# coil-control-rev.net
KiCad netlist of a schematic drawn in EAGLE
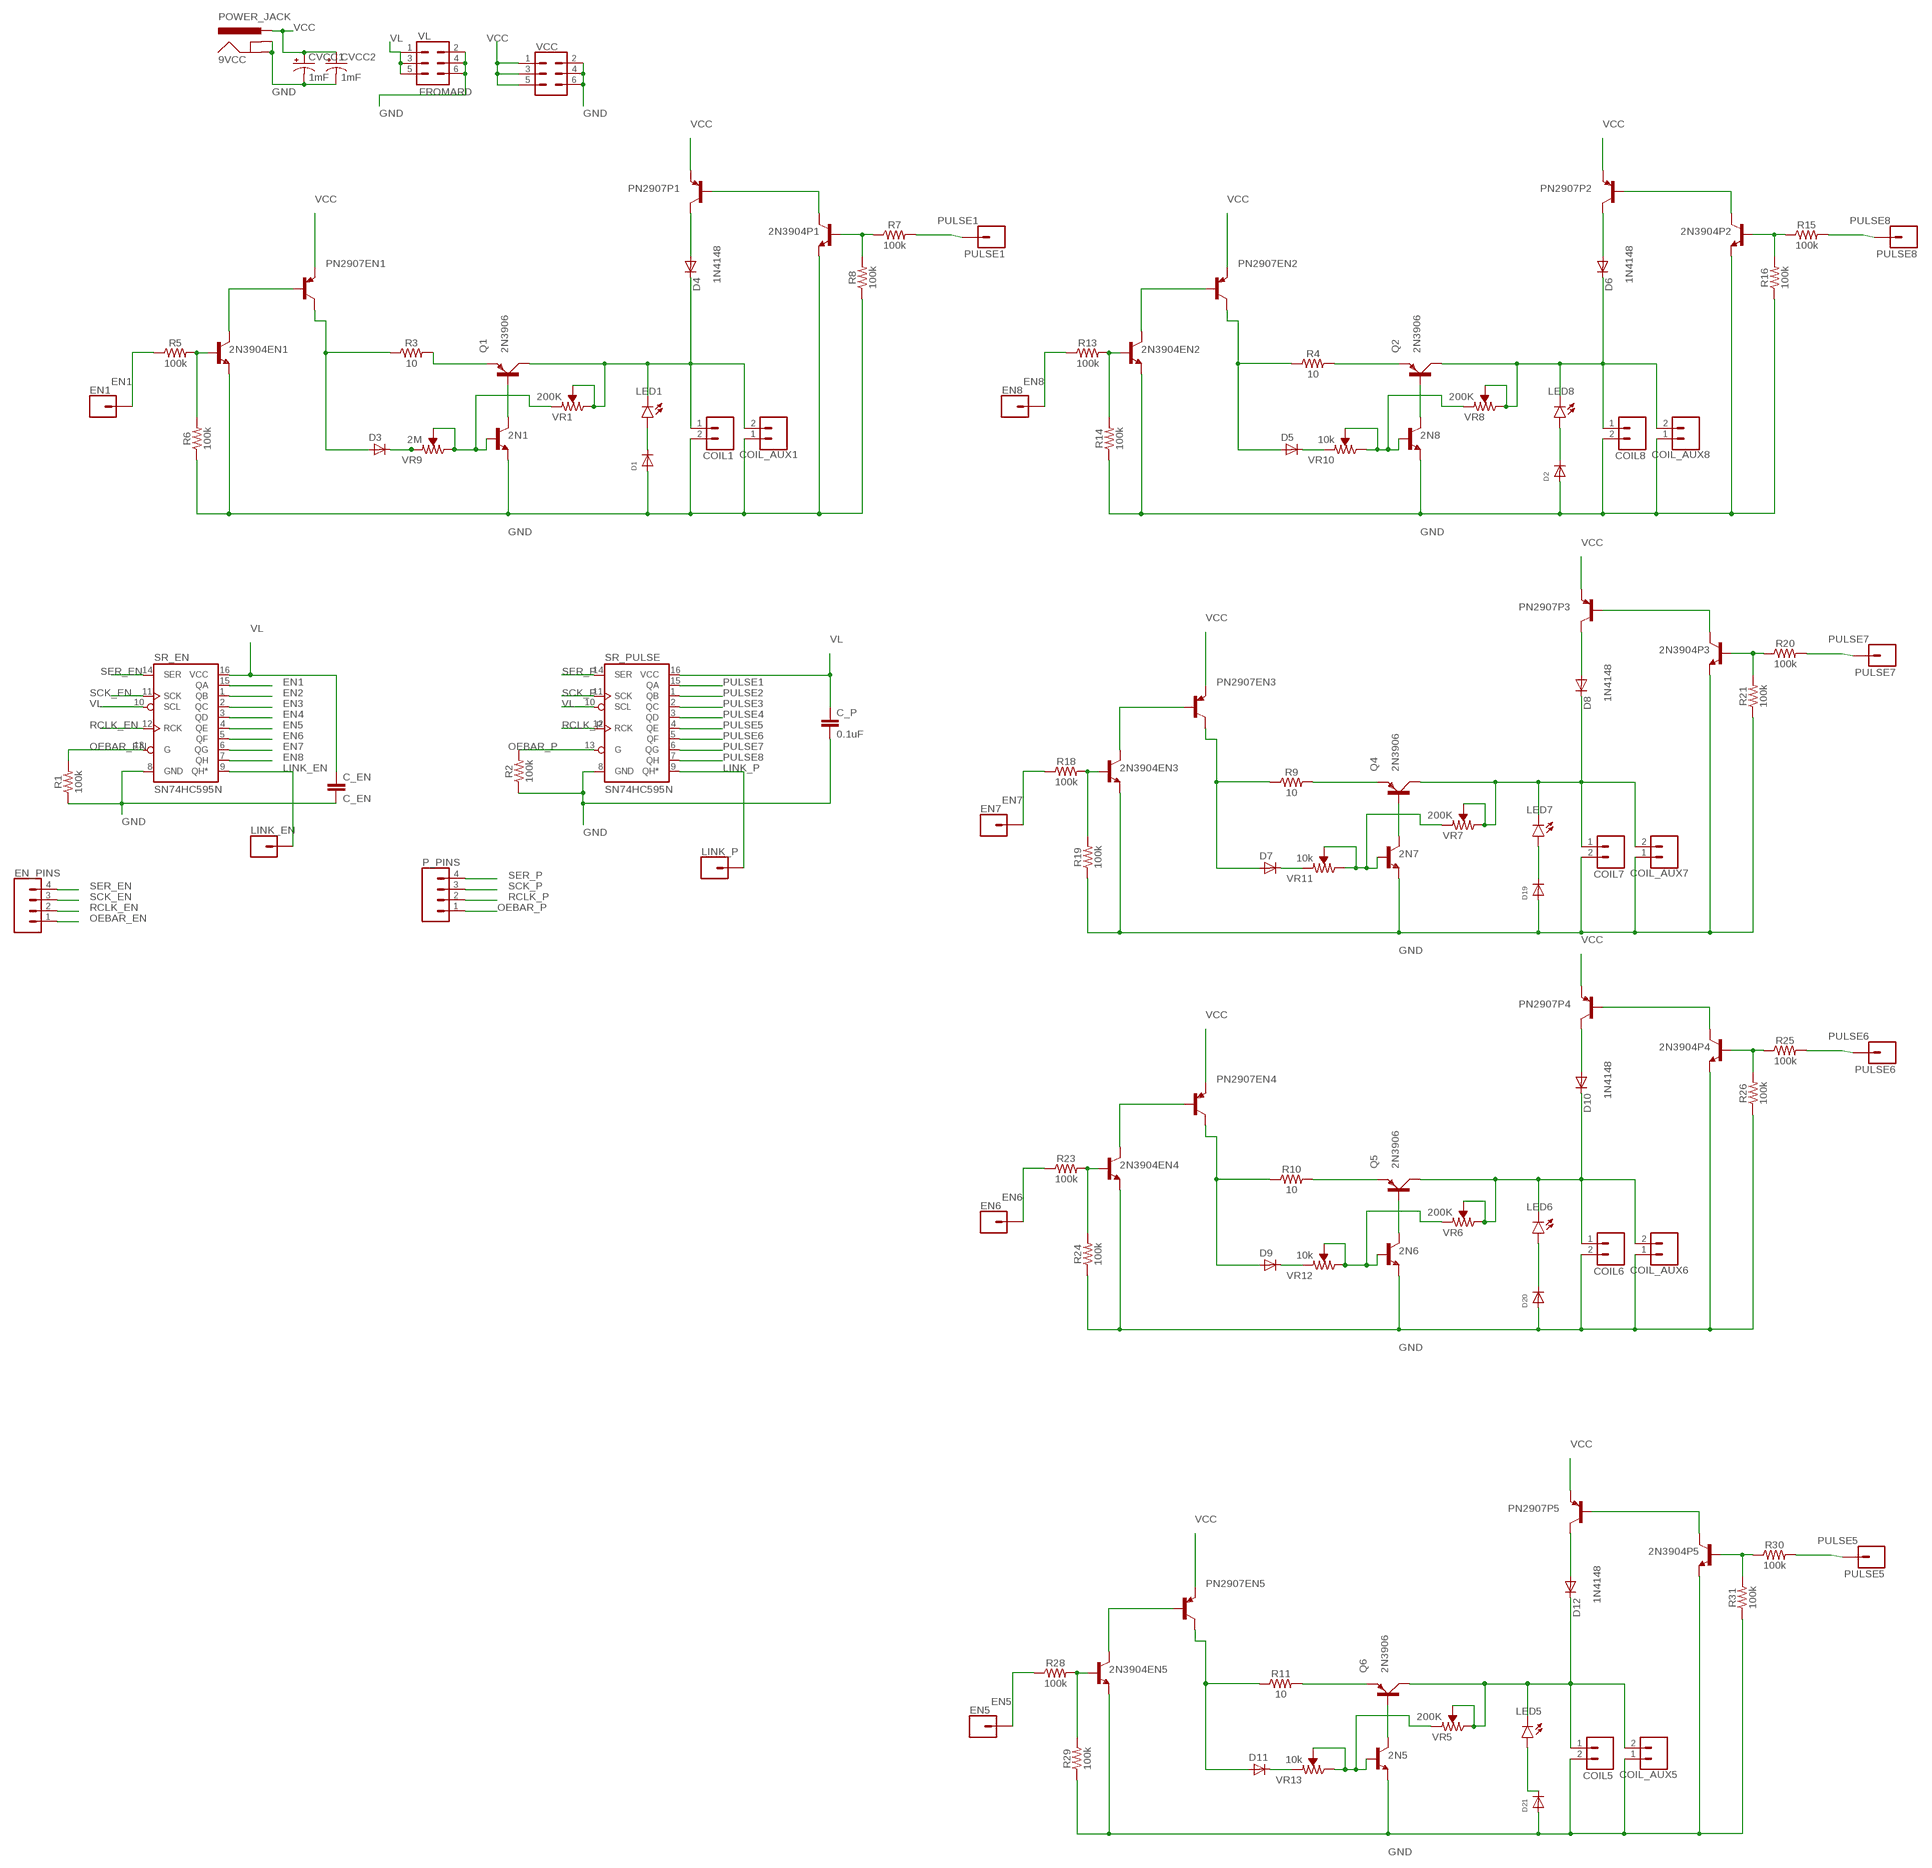
[diagram p0: schematic, sheet 1, part 1 of 2]
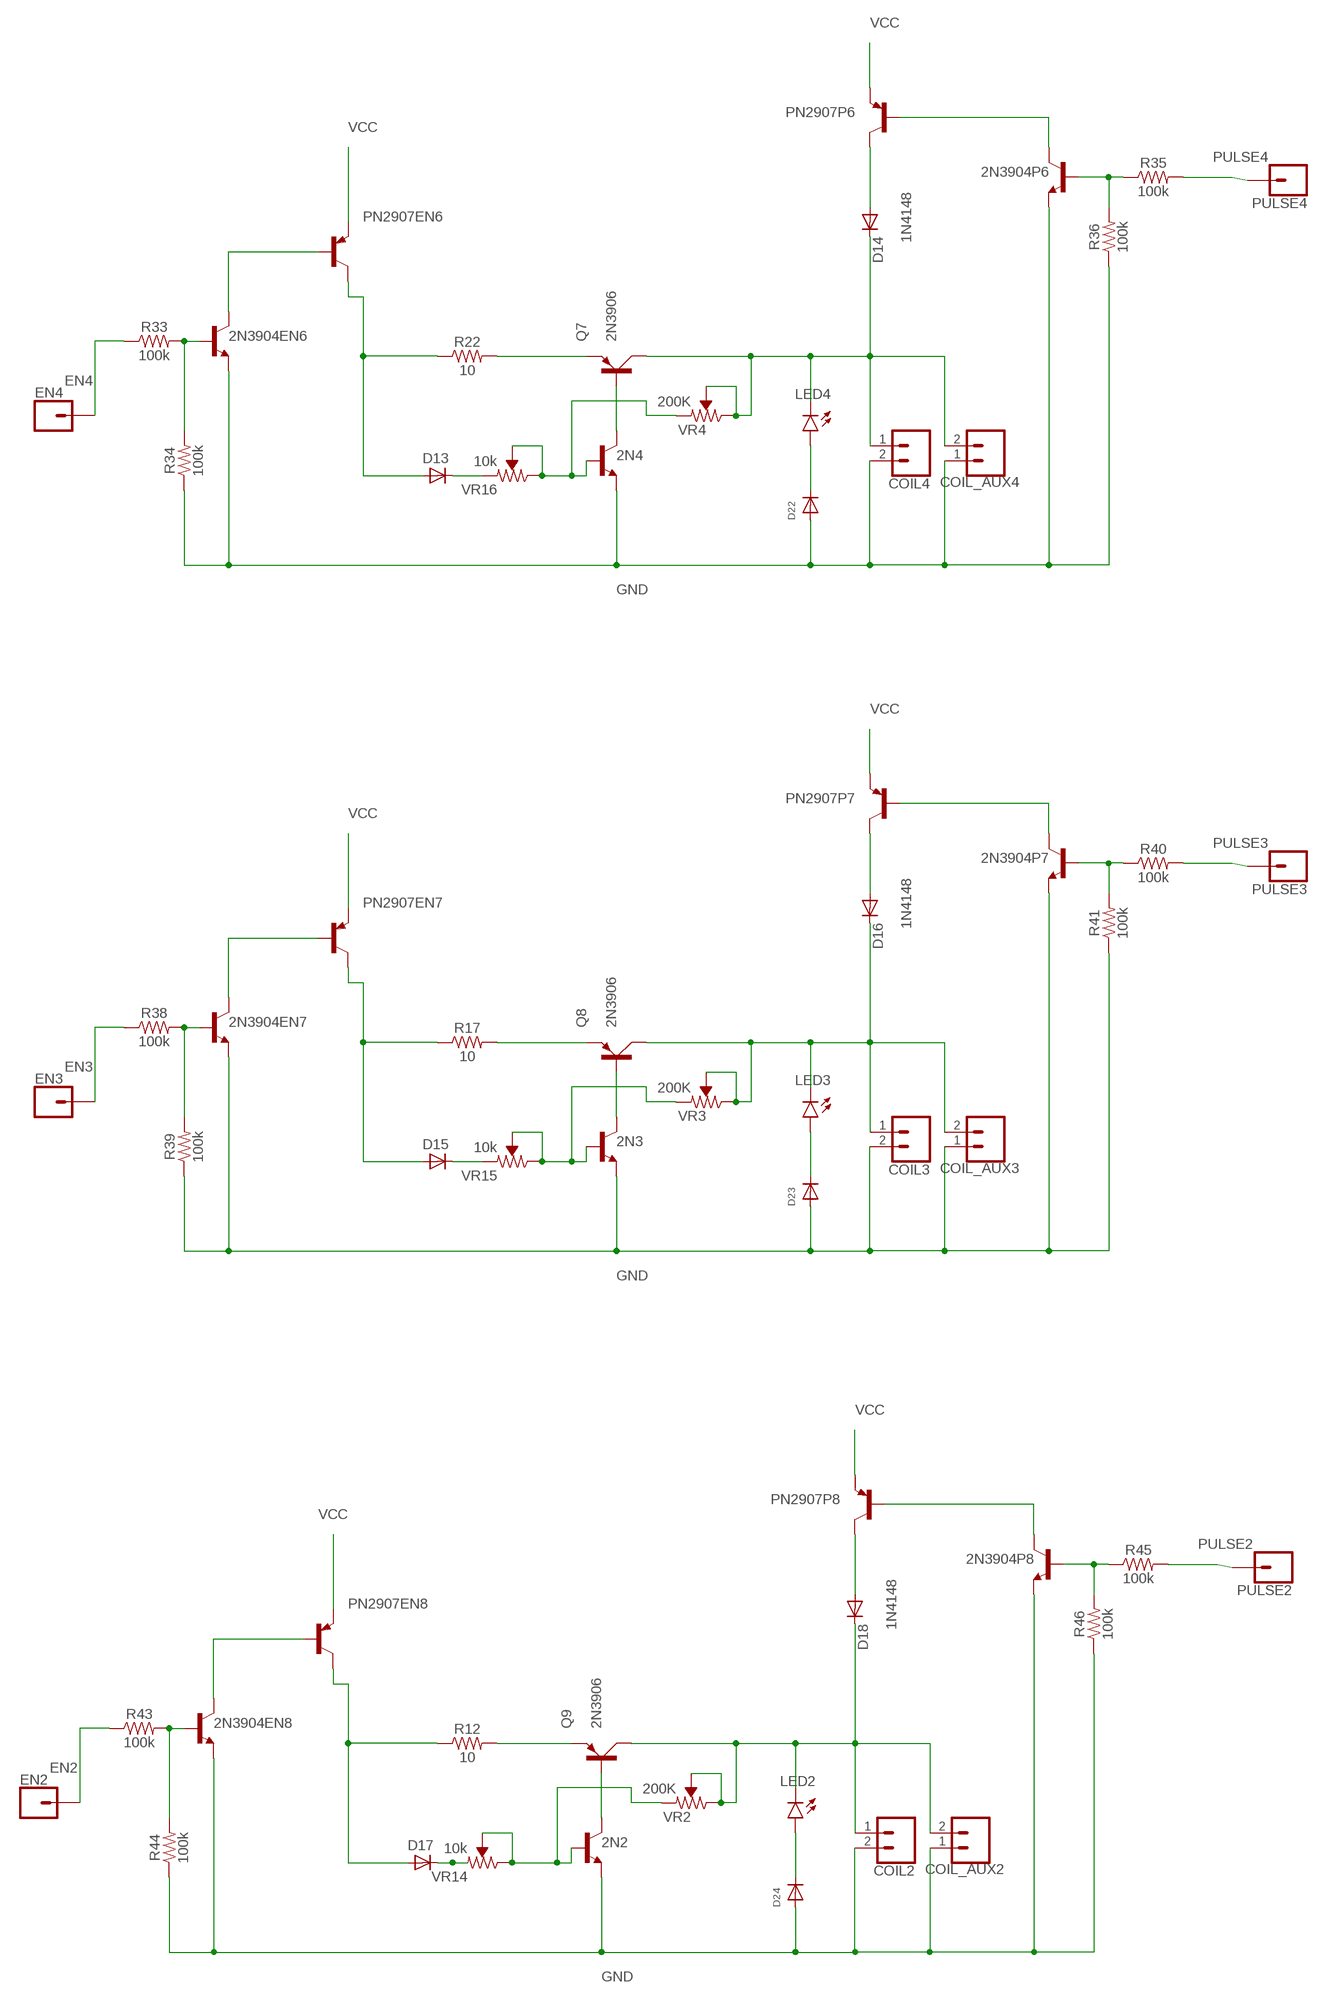
[diagram p1: schematic, sheet 1, part 2 of 2]

(export (version "E")
  (design (tool "Eeschema 10.0.6"))
  (components
    (comp (ref "2N1")
      (value "2N2222")
      (footprint "eagle-import:TO92-EBC-OVAL")
      (libsource (lib "eagle-import") (part "2N2222"))
    )
    (comp (ref "2N2")
      (value "2N2222")
      (footprint "eagle-import:TO92-EBC-OVAL")
      (libsource (lib "eagle-import") (part "2N2222"))
    )
    (comp (ref "2N3")
      (value "2N2222")
      (footprint "eagle-import:TO92-EBC-OVAL")
      (libsource (lib "eagle-import") (part "2N2222"))
    )
    (comp (ref "2N4")
      (value "2N2222")
      (footprint "eagle-import:TO92-EBC-OVAL")
      (libsource (lib "eagle-import") (part "2N2222"))
    )
    (comp (ref "2N5")
      (value "2N2222")
      (footprint "eagle-import:TO92-EBC-OVAL")
      (libsource (lib "eagle-import") (part "2N2222"))
    )
    (comp (ref "2N6")
      (value "2N2222")
      (footprint "eagle-import:TO92-EBC-OVAL")
      (libsource (lib "eagle-import") (part "2N2222"))
    )
    (comp (ref "2N7")
      (value "2N2222")
      (footprint "eagle-import:TO92-EBC-OVAL")
      (libsource (lib "eagle-import") (part "2N2222"))
    )
    (comp (ref "2N8")
      (value "2N2222")
      (footprint "eagle-import:TO92-EBC-OVAL")
      (libsource (lib "eagle-import") (part "2N2222"))
    )
    (comp (ref "2N3904EN1")
      (value "2N3904")
      (footprint "eagle-import:TO92")
      (libsource (lib "eagle-import") (part "2N3904"))
    )
    (comp (ref "2N3904EN2")
      (value "2N3904")
      (footprint "eagle-import:TO92")
      (libsource (lib "eagle-import") (part "2N3904"))
    )
    (comp (ref "2N3904EN3")
      (value "2N3904")
      (footprint "eagle-import:TO92")
      (libsource (lib "eagle-import") (part "2N3904"))
    )
    (comp (ref "2N3904EN4")
      (value "2N3904")
      (footprint "eagle-import:TO92")
      (libsource (lib "eagle-import") (part "2N3904"))
    )
    (comp (ref "2N3904EN5")
      (value "2N3904")
      (footprint "eagle-import:TO92")
      (libsource (lib "eagle-import") (part "2N3904"))
    )
    (comp (ref "2N3904EN6")
      (value "2N3904")
      (footprint "eagle-import:TO92")
      (libsource (lib "eagle-import") (part "2N3904"))
    )
    (comp (ref "2N3904EN7")
      (value "2N3904")
      (footprint "eagle-import:TO92")
      (libsource (lib "eagle-import") (part "2N3904"))
    )
    (comp (ref "2N3904EN8")
      (value "2N3904")
      (footprint "eagle-import:TO92")
      (libsource (lib "eagle-import") (part "2N3904"))
    )
    (comp (ref "2N3904P1")
      (value "2N3904")
      (footprint "eagle-import:TO92")
      (libsource (lib "eagle-import") (part "2N3904"))
    )
    (comp (ref "2N3904P2")
      (value "2N3904")
      (footprint "eagle-import:TO92")
      (libsource (lib "eagle-import") (part "2N3904"))
    )
    (comp (ref "2N3904P3")
      (value "2N3904")
      (footprint "eagle-import:TO92")
      (libsource (lib "eagle-import") (part "2N3904"))
    )
    (comp (ref "2N3904P4")
      (value "2N3904")
      (footprint "eagle-import:TO92")
      (libsource (lib "eagle-import") (part "2N3904"))
    )
    (comp (ref "2N3904P5")
      (value "2N3904")
      (footprint "eagle-import:TO92")
      (libsource (lib "eagle-import") (part "2N3904"))
    )
    (comp (ref "2N3904P6")
      (value "2N3904")
      (footprint "eagle-import:TO92")
      (libsource (lib "eagle-import") (part "2N3904"))
    )
    (comp (ref "2N3904P7")
      (value "2N3904")
      (footprint "eagle-import:TO92")
      (libsource (lib "eagle-import") (part "2N3904"))
    )
    (comp (ref "2N3904P8")
      (value "2N3904")
      (footprint "eagle-import:TO92")
      (libsource (lib "eagle-import") (part "2N3904"))
    )
    (comp (ref "9VCC")
      (value "POWER_JACK")
      (footprint "eagle-import:POWER_JACK_PTH")
      (libsource (lib "eagle-import") (part "POWER_JACK"))
    )
    (comp (ref "COIL1")
      (value "CONN_02")
      (footprint "eagle-import:1X02")
      (libsource (lib "eagle-import") (part "CONN_02"))
    )
    (comp (ref "COIL2")
      (value "CONN_02")
      (footprint "eagle-import:1X02")
      (libsource (lib "eagle-import") (part "CONN_02"))
    )
    (comp (ref "COIL3")
      (value "CONN_02")
      (footprint "eagle-import:1X02")
      (libsource (lib "eagle-import") (part "CONN_02"))
    )
    (comp (ref "COIL4")
      (value "CONN_02")
      (footprint "eagle-import:1X02")
      (libsource (lib "eagle-import") (part "CONN_02"))
    )
    (comp (ref "COIL5")
      (value "CONN_02")
      (footprint "eagle-import:1X02")
      (libsource (lib "eagle-import") (part "CONN_02"))
    )
    (comp (ref "COIL6")
      (value "CONN_02")
      (footprint "eagle-import:1X02")
      (libsource (lib "eagle-import") (part "CONN_02"))
    )
    (comp (ref "COIL7")
      (value "CONN_02")
      (footprint "eagle-import:1X02")
      (libsource (lib "eagle-import") (part "CONN_02"))
    )
    (comp (ref "COIL8")
      (value "CONN_02")
      (footprint "eagle-import:1X02")
      (libsource (lib "eagle-import") (part "CONN_02"))
    )
    (comp (ref "COIL_AUX1")
      (value "CONN_02")
      (footprint "eagle-import:1X02")
      (libsource (lib "eagle-import") (part "CONN_02"))
    )
    (comp (ref "COIL_AUX2")
      (value "CONN_02")
      (footprint "eagle-import:1X02")
      (libsource (lib "eagle-import") (part "CONN_02"))
    )
    (comp (ref "COIL_AUX3")
      (value "CONN_02")
      (footprint "eagle-import:1X02")
      (libsource (lib "eagle-import") (part "CONN_02"))
    )
    (comp (ref "COIL_AUX4")
      (value "CONN_02")
      (footprint "eagle-import:1X02")
      (libsource (lib "eagle-import") (part "CONN_02"))
    )
    (comp (ref "COIL_AUX5")
      (value "CONN_02")
      (footprint "eagle-import:1X02")
      (libsource (lib "eagle-import") (part "CONN_02"))
    )
    (comp (ref "COIL_AUX6")
      (value "CONN_02")
      (footprint "eagle-import:1X02")
      (libsource (lib "eagle-import") (part "CONN_02"))
    )
    (comp (ref "COIL_AUX7")
      (value "CONN_02")
      (footprint "eagle-import:1X02")
      (libsource (lib "eagle-import") (part "CONN_02"))
    )
    (comp (ref "COIL_AUX8")
      (value "CONN_02")
      (footprint "eagle-import:1X02")
      (libsource (lib "eagle-import") (part "CONN_02"))
    )
    (comp (ref "CVCC1")
      (value "1mF")
      (footprint "eagle-import:CPOL-RADIAL-5MM-10MM")
      (libsource (lib "eagle-import") (part "1000UF-RADIAL-5MM-25V-20%"))
    )
    (comp (ref "CVCC2")
      (value "1mF")
      (footprint "eagle-import:CPOL-RADIAL-5MM-10MM")
      (libsource (lib "eagle-import") (part "1000UF-RADIAL-5MM-25V-20%"))
    )
    (comp (ref "C_EN")
      (value "C_EN")
      (footprint "eagle-import:CAP-PTH-SMALL-KIT")
      (libsource (lib "eagle-import") (part "0.1UF-KIT-EZ-50V-20%"))
    )
    (comp (ref "C_P")
      (value "0.1uF")
      (footprint "eagle-import:CAP-PTH-SMALL-KIT")
      (libsource (lib "eagle-import") (part "0.1UF-KIT-EZ-50V-20%"))
    )
    (comp (ref "D1")
      (value "DIODEDO-1N4148")
      (footprint "eagle-import:DO-1N4148")
      (libsource (lib "eagle-import") (part "DIODEDO-1N4148"))
    )
    (comp (ref "D2")
      (value "DIODEDO-1N4148")
      (footprint "eagle-import:DO-1N4148")
      (libsource (lib "eagle-import") (part "DIODEDO-1N4148"))
    )
    (comp (ref "D3")
      (value "DIODEDO-1N4148")
      (footprint "eagle-import:DO-1N4148")
      (libsource (lib "eagle-import") (part "DIODEDO-1N4148"))
    )
    (comp (ref "D4")
      (value "1N4148")
      (footprint "eagle-import:DO-1N4148")
      (libsource (lib "eagle-import") (part "DIODEDO-1N4148"))
    )
    (comp (ref "D5")
      (value "DIODEDO-1N4148")
      (footprint "eagle-import:DO-1N4148")
      (libsource (lib "eagle-import") (part "DIODEDO-1N4148"))
    )
    (comp (ref "D6")
      (value "1N4148")
      (footprint "eagle-import:DO-1N4148")
      (libsource (lib "eagle-import") (part "DIODEDO-1N4148"))
    )
    (comp (ref "D7")
      (value "DIODEDO-1N4148")
      (footprint "eagle-import:DO-1N4148")
      (libsource (lib "eagle-import") (part "DIODEDO-1N4148"))
    )
    (comp (ref "D8")
      (value "1N4148")
      (footprint "eagle-import:DO-1N4148")
      (libsource (lib "eagle-import") (part "DIODEDO-1N4148"))
    )
    (comp (ref "D9")
      (value "DIODEDO-1N4148")
      (footprint "eagle-import:DO-1N4148")
      (libsource (lib "eagle-import") (part "DIODEDO-1N4148"))
    )
    (comp (ref "D10")
      (value "1N4148")
      (footprint "eagle-import:DO-1N4148")
      (libsource (lib "eagle-import") (part "DIODEDO-1N4148"))
    )
    (comp (ref "D11")
      (value "200mA/100V/1V")
      (footprint "eagle-import:DO-1N4148")
      (libsource (lib "eagle-import") (part "DIODEDO-1N4148"))
    )
    (comp (ref "D12")
      (value "1N4148")
      (footprint "eagle-import:DO-1N4148")
      (libsource (lib "eagle-import") (part "DIODEDO-1N4148"))
    )
    (comp (ref "D13")
      (value "DIODEDO-1N4148")
      (footprint "eagle-import:DO-1N4148")
      (libsource (lib "eagle-import") (part "DIODEDO-1N4148"))
    )
    (comp (ref "D14")
      (value "1N4148")
      (footprint "eagle-import:DO-1N4148")
      (libsource (lib "eagle-import") (part "DIODEDO-1N4148"))
    )
    (comp (ref "D15")
      (value "DIODEDO-1N4148")
      (footprint "eagle-import:DO-1N4148")
      (libsource (lib "eagle-import") (part "DIODEDO-1N4148"))
    )
    (comp (ref "D16")
      (value "1N4148")
      (footprint "eagle-import:DO-1N4148")
      (libsource (lib "eagle-import") (part "DIODEDO-1N4148"))
    )
    (comp (ref "D17")
      (value "DIODEDO-1N4148")
      (footprint "eagle-import:DO-1N4148")
      (libsource (lib "eagle-import") (part "DIODEDO-1N4148"))
    )
    (comp (ref "D18")
      (value "1N4148")
      (footprint "eagle-import:DO-1N4148")
      (libsource (lib "eagle-import") (part "DIODEDO-1N4148"))
    )
    (comp (ref "D19")
      (value "DIODEDO-1N4148")
      (footprint "eagle-import:DO-1N4148")
      (libsource (lib "eagle-import") (part "DIODEDO-1N4148"))
    )
    (comp (ref "D20")
      (value "DIODEDO-1N4148")
      (footprint "eagle-import:DO-1N4148")
      (libsource (lib "eagle-import") (part "DIODEDO-1N4148"))
    )
    (comp (ref "D21")
      (value "DIODEDO-1N4148")
      (footprint "eagle-import:DO-1N4148")
      (libsource (lib "eagle-import") (part "DIODEDO-1N4148"))
    )
    (comp (ref "D22")
      (value "DIODEDO-1N4148")
      (footprint "eagle-import:DO-1N4148")
      (libsource (lib "eagle-import") (part "DIODEDO-1N4148"))
    )
    (comp (ref "D23")
      (value "DIODEDO-1N4148")
      (footprint "eagle-import:DO-1N4148")
      (libsource (lib "eagle-import") (part "DIODEDO-1N4148"))
    )
    (comp (ref "D24")
      (value "DIODEDO-1N4148")
      (footprint "eagle-import:DO-1N4148")
      (libsource (lib "eagle-import") (part "DIODEDO-1N4148"))
    )
    (comp (ref "EN1")
      (value "CONN_01")
      (footprint "eagle-import:1X01")
      (libsource (lib "eagle-import") (part "CONN_01"))
    )
    (comp (ref "EN2")
      (value "CONN_01")
      (footprint "eagle-import:1X01")
      (libsource (lib "eagle-import") (part "CONN_01"))
    )
    (comp (ref "EN3")
      (value "CONN_01")
      (footprint "eagle-import:1X01")
      (libsource (lib "eagle-import") (part "CONN_01"))
    )
    (comp (ref "EN4")
      (value "CONN_01")
      (footprint "eagle-import:1X01")
      (libsource (lib "eagle-import") (part "CONN_01"))
    )
    (comp (ref "EN5")
      (value "CONN_01")
      (footprint "eagle-import:1X01")
      (libsource (lib "eagle-import") (part "CONN_01"))
    )
    (comp (ref "EN6")
      (value "CONN_01")
      (footprint "eagle-import:1X01")
      (libsource (lib "eagle-import") (part "CONN_01"))
    )
    (comp (ref "EN7")
      (value "CONN_01")
      (footprint "eagle-import:1X01")
      (libsource (lib "eagle-import") (part "CONN_01"))
    )
    (comp (ref "EN8")
      (value "EN2")
      (footprint "eagle-import:1X01")
      (libsource (lib "eagle-import") (part "CONN_01"))
    )
    (comp (ref "EN_PINS")
      (value "CONN_04PTH")
      (footprint "eagle-import:1X04")
      (libsource (lib "eagle-import") (part "CONN_04PTH"))
    )
    (comp (ref "LED1")
      (value "LED3MM")
      (footprint "eagle-import:LED_3MM")
      (libsource (lib "eagle-import") (part "LED3MM"))
    )
    (comp (ref "LED2")
      (value "LED3MM")
      (footprint "eagle-import:LED_3MM")
      (libsource (lib "eagle-import") (part "LED3MM"))
    )
    (comp (ref "LED3")
      (value "LED3MM")
      (footprint "eagle-import:LED_3MM")
      (libsource (lib "eagle-import") (part "LED3MM"))
    )
    (comp (ref "LED4")
      (value "LED3MM")
      (footprint "eagle-import:LED_3MM")
      (libsource (lib "eagle-import") (part "LED3MM"))
    )
    (comp (ref "LED5")
      (value "LED3MM")
      (footprint "eagle-import:LED_3MM")
      (libsource (lib "eagle-import") (part "LED3MM"))
    )
    (comp (ref "LED6")
      (value "LED3MM")
      (footprint "eagle-import:LED_3MM")
      (libsource (lib "eagle-import") (part "LED3MM"))
    )
    (comp (ref "LED7")
      (value "LED3MM")
      (footprint "eagle-import:LED_3MM")
      (libsource (lib "eagle-import") (part "LED3MM"))
    )
    (comp (ref "LED8")
      (value "LED3MM")
      (footprint "eagle-import:LED_3MM")
      (libsource (lib "eagle-import") (part "LED3MM"))
    )
    (comp (ref "LINK_EN")
      (value "CONN_01")
      (footprint "eagle-import:1X01")
      (libsource (lib "eagle-import") (part "CONN_01"))
    )
    (comp (ref "LINK_P")
      (value "CONN_01")
      (footprint "eagle-import:1X01")
      (libsource (lib "eagle-import") (part "CONN_01"))
    )
    (comp (ref "PN2907EN1")
      (value "2N2907")
      (footprint "eagle-import:TO92-EBC-OVAL")
      (libsource (lib "eagle-import") (part "2N2907"))
    )
    (comp (ref "PN2907EN2")
      (value "2N2907")
      (footprint "eagle-import:TO92-EBC-OVAL")
      (libsource (lib "eagle-import") (part "2N2907"))
    )
    (comp (ref "PN2907EN3")
      (value "2N2907")
      (footprint "eagle-import:TO92-EBC-OVAL")
      (libsource (lib "eagle-import") (part "2N2907"))
    )
    (comp (ref "PN2907EN4")
      (value "2N2907")
      (footprint "eagle-import:TO92-EBC-OVAL")
      (libsource (lib "eagle-import") (part "2N2907"))
    )
    (comp (ref "PN2907EN5")
      (value "2N2907")
      (footprint "eagle-import:TO92-EBC-OVAL")
      (libsource (lib "eagle-import") (part "2N2907"))
    )
    (comp (ref "PN2907EN6")
      (value "2N2907")
      (footprint "eagle-import:TO92-EBC-OVAL")
      (libsource (lib "eagle-import") (part "2N2907"))
    )
    (comp (ref "PN2907EN7")
      (value "2N2907")
      (footprint "eagle-import:TO92-EBC-OVAL")
      (libsource (lib "eagle-import") (part "2N2907"))
    )
    (comp (ref "PN2907EN8")
      (value "2N2907")
      (footprint "eagle-import:TO92-EBC-OVAL")
      (libsource (lib "eagle-import") (part "2N2907"))
    )
    (comp (ref "PN2907P1")
      (value "2N2907")
      (footprint "eagle-import:TO92-EBC-OVAL")
      (libsource (lib "eagle-import") (part "2N2907"))
    )
    (comp (ref "PN2907P2")
      (value "2N2907")
      (footprint "eagle-import:TO92-EBC-OVAL")
      (libsource (lib "eagle-import") (part "2N2907"))
    )
    (comp (ref "PN2907P3")
      (value "2N2907")
      (footprint "eagle-import:TO92-EBC-OVAL")
      (libsource (lib "eagle-import") (part "2N2907"))
    )
    (comp (ref "PN2907P4")
      (value "2N2907")
      (footprint "eagle-import:TO92-EBC-OVAL")
      (libsource (lib "eagle-import") (part "2N2907"))
    )
    (comp (ref "PN2907P5")
      (value "2N2907")
      (footprint "eagle-import:TO92-EBC-OVAL")
      (libsource (lib "eagle-import") (part "2N2907"))
    )
    (comp (ref "PN2907P6")
      (value "2N2907")
      (footprint "eagle-import:TO92-EBC-OVAL")
      (libsource (lib "eagle-import") (part "2N2907"))
    )
    (comp (ref "PN2907P7")
      (value "2N2907")
      (footprint "eagle-import:TO92-EBC-OVAL")
      (libsource (lib "eagle-import") (part "2N2907"))
    )
    (comp (ref "PN2907P8")
      (value "2N2907")
      (footprint "eagle-import:TO92-EBC-OVAL")
      (libsource (lib "eagle-import") (part "2N2907"))
    )
    (comp (ref "PULSE1")
      (value "CONN_01")
      (footprint "eagle-import:1X01")
      (libsource (lib "eagle-import") (part "CONN_01"))
    )
    (comp (ref "PULSE2")
      (value "CONN_01")
      (footprint "eagle-import:1X01")
      (libsource (lib "eagle-import") (part "CONN_01"))
    )
    (comp (ref "PULSE3")
      (value "CONN_01")
      (footprint "eagle-import:1X01")
      (libsource (lib "eagle-import") (part "CONN_01"))
    )
    (comp (ref "PULSE4")
      (value "CONN_01")
      (footprint "eagle-import:1X01")
      (libsource (lib "eagle-import") (part "CONN_01"))
    )
    (comp (ref "PULSE5")
      (value "CONN_01")
      (footprint "eagle-import:1X01")
      (libsource (lib "eagle-import") (part "CONN_01"))
    )
    (comp (ref "PULSE6")
      (value "CONN_01")
      (footprint "eagle-import:1X01")
      (libsource (lib "eagle-import") (part "CONN_01"))
    )
    (comp (ref "PULSE7")
      (value "PULSE3")
      (footprint "eagle-import:1X01")
      (libsource (lib "eagle-import") (part "CONN_01"))
    )
    (comp (ref "PULSE8")
      (value "PULSE2")
      (footprint "eagle-import:1X01")
      (libsource (lib "eagle-import") (part "CONN_01"))
    )
    (comp (ref "P_PINS")
      (value "CONN_04PTH")
      (footprint "eagle-import:1X04")
      (libsource (lib "eagle-import") (part "CONN_04PTH"))
    )
    (comp (ref "Q1")
      (value "2N3906")
      (footprint "eagle-import:TO92D")
      (libsource (lib "eagle-import") (part "2N3906"))
    )
    (comp (ref "Q2")
      (value "2N3906")
      (footprint "eagle-import:TO92D")
      (libsource (lib "eagle-import") (part "2N3906"))
    )
    (comp (ref "Q4")
      (value "2N3906")
      (footprint "eagle-import:TO92D")
      (libsource (lib "eagle-import") (part "2N3906"))
    )
    (comp (ref "Q5")
      (value "2N3906")
      (footprint "eagle-import:TO92D")
      (libsource (lib "eagle-import") (part "2N3906"))
    )
    (comp (ref "Q6")
      (value "2N3906")
      (footprint "eagle-import:TO92D")
      (libsource (lib "eagle-import") (part "2N3906"))
    )
    (comp (ref "Q7")
      (value "2N3906")
      (footprint "eagle-import:TO92D")
      (libsource (lib "eagle-import") (part "2N3906"))
    )
    (comp (ref "Q8")
      (value "2N3906")
      (footprint "eagle-import:TO92D")
      (libsource (lib "eagle-import") (part "2N3906"))
    )
    (comp (ref "Q9")
      (value "2N3906")
      (footprint "eagle-import:TO92D")
      (libsource (lib "eagle-import") (part "2N3906"))
    )
    (comp (ref "R1")
      (value "100k")
      (footprint "eagle-import:AXIAL-0.3")
      (libsource (lib "eagle-import") (part "100KOHM-HORIZ-1/4W-1%"))
    )
    (comp (ref "R2")
      (value "100k")
      (footprint "eagle-import:AXIAL-0.3")
      (libsource (lib "eagle-import") (part "100KOHM-HORIZ-1/4W-1%"))
    )
    (comp (ref "R3")
      (value "10")
      (footprint "eagle-import:AXIAL-0.1")
      (libsource (lib "eagle-import") (part "10OHM-VERT-1/4W-1%"))
    )
    (comp (ref "R4")
      (value "10")
      (footprint "eagle-import:AXIAL-0.1")
      (libsource (lib "eagle-import") (part "10OHM-VERT-1/4W-1%"))
    )
    (comp (ref "R5")
      (value "100k")
      (footprint "eagle-import:AXIAL-0.3")
      (libsource (lib "eagle-import") (part "100KOHM-HORIZ-1/4W-1%"))
    )
    (comp (ref "R6")
      (value "100k")
      (footprint "eagle-import:AXIAL-0.3")
      (libsource (lib "eagle-import") (part "100KOHM-HORIZ-1/4W-1%"))
    )
    (comp (ref "R7")
      (value "100k")
      (footprint "eagle-import:AXIAL-0.3")
      (libsource (lib "eagle-import") (part "100KOHM-HORIZ-1/4W-1%"))
    )
    (comp (ref "R8")
      (value "100k")
      (footprint "eagle-import:AXIAL-0.3")
      (libsource (lib "eagle-import") (part "100KOHM-HORIZ-1/4W-1%"))
    )
    (comp (ref "R9")
      (value "10")
      (footprint "eagle-import:AXIAL-0.1")
      (libsource (lib "eagle-import") (part "10OHM-VERT-1/4W-1%"))
    )
    (comp (ref "R10")
      (value "10")
      (footprint "eagle-import:AXIAL-0.1")
      (libsource (lib "eagle-import") (part "10OHM-VERT-1/4W-1%"))
    )
    (comp (ref "R11")
      (value "10")
      (footprint "eagle-import:AXIAL-0.1")
      (libsource (lib "eagle-import") (part "10OHM-VERT-1/4W-1%"))
    )
    (comp (ref "R12")
      (value "10")
      (footprint "eagle-import:AXIAL-0.1")
      (libsource (lib "eagle-import") (part "10OHM-VERT-1/4W-1%"))
    )
    (comp (ref "R13")
      (value "100k")
      (footprint "eagle-import:AXIAL-0.3")
      (libsource (lib "eagle-import") (part "100KOHM-HORIZ-1/4W-1%"))
    )
    (comp (ref "R14")
      (value "100k")
      (footprint "eagle-import:AXIAL-0.3")
      (libsource (lib "eagle-import") (part "100KOHM-HORIZ-1/4W-1%"))
    )
    (comp (ref "R15")
      (value "100k")
      (footprint "eagle-import:AXIAL-0.3")
      (libsource (lib "eagle-import") (part "100KOHM-HORIZ-1/4W-1%"))
    )
    (comp (ref "R16")
      (value "100k")
      (footprint "eagle-import:AXIAL-0.3")
      (libsource (lib "eagle-import") (part "100KOHM-HORIZ-1/4W-1%"))
    )
    (comp (ref "R17")
      (value "10")
      (footprint "eagle-import:AXIAL-0.1")
      (libsource (lib "eagle-import") (part "10OHM-VERT-1/4W-1%"))
    )
    (comp (ref "R18")
      (value "100k")
      (footprint "eagle-import:AXIAL-0.3")
      (libsource (lib "eagle-import") (part "100KOHM-HORIZ-1/4W-1%"))
    )
    (comp (ref "R19")
      (value "100k")
      (footprint "eagle-import:AXIAL-0.3")
      (libsource (lib "eagle-import") (part "100KOHM-HORIZ-1/4W-1%"))
    )
    (comp (ref "R20")
      (value "100k")
      (footprint "eagle-import:AXIAL-0.3")
      (libsource (lib "eagle-import") (part "100KOHM-HORIZ-1/4W-1%"))
    )
    (comp (ref "R21")
      (value "100k")
      (footprint "eagle-import:AXIAL-0.3")
      (libsource (lib "eagle-import") (part "100KOHM-HORIZ-1/4W-1%"))
    )
    (comp (ref "R22")
      (value "10")
      (footprint "eagle-import:AXIAL-0.1")
      (libsource (lib "eagle-import") (part "10OHM-VERT-1/4W-1%"))
    )
    (comp (ref "R23")
      (value "100k")
      (footprint "eagle-import:AXIAL-0.3")
      (libsource (lib "eagle-import") (part "100KOHM-HORIZ-1/4W-1%"))
    )
    (comp (ref "R24")
      (value "100k")
      (footprint "eagle-import:AXIAL-0.3")
      (libsource (lib "eagle-import") (part "100KOHM-HORIZ-1/4W-1%"))
    )
    (comp (ref "R25")
      (value "100k")
      (footprint "eagle-import:AXIAL-0.3")
      (libsource (lib "eagle-import") (part "100KOHM-HORIZ-1/4W-1%"))
    )
    (comp (ref "R26")
      (value "100k")
      (footprint "eagle-import:AXIAL-0.3")
      (libsource (lib "eagle-import") (part "100KOHM-HORIZ-1/4W-1%"))
    )
    (comp (ref "R28")
      (value "100k")
      (footprint "eagle-import:AXIAL-0.3")
      (libsource (lib "eagle-import") (part "100KOHM-HORIZ-1/4W-1%"))
    )
    (comp (ref "R29")
      (value "100k")
      (footprint "eagle-import:AXIAL-0.3")
      (libsource (lib "eagle-import") (part "100KOHM-HORIZ-1/4W-1%"))
    )
    (comp (ref "R30")
      (value "100k")
      (footprint "eagle-import:AXIAL-0.3")
      (libsource (lib "eagle-import") (part "100KOHM-HORIZ-1/4W-1%"))
    )
    (comp (ref "R31")
      (value "100k")
      (footprint "eagle-import:AXIAL-0.3")
      (libsource (lib "eagle-import") (part "100KOHM-HORIZ-1/4W-1%"))
    )
    (comp (ref "R33")
      (value "100k")
      (footprint "eagle-import:AXIAL-0.3")
      (libsource (lib "eagle-import") (part "100KOHM-HORIZ-1/4W-1%"))
    )
    (comp (ref "R34")
      (value "100k")
      (footprint "eagle-import:AXIAL-0.3")
      (libsource (lib "eagle-import") (part "100KOHM-HORIZ-1/4W-1%"))
    )
    (comp (ref "R35")
      (value "100k")
      (footprint "eagle-import:AXIAL-0.3")
      (libsource (lib "eagle-import") (part "100KOHM-HORIZ-1/4W-1%"))
    )
    (comp (ref "R36")
      (value "100k")
      (footprint "eagle-import:AXIAL-0.3")
      (libsource (lib "eagle-import") (part "100KOHM-HORIZ-1/4W-1%"))
    )
    (comp (ref "R38")
      (value "100k")
      (footprint "eagle-import:AXIAL-0.3")
      (libsource (lib "eagle-import") (part "100KOHM-HORIZ-1/4W-1%"))
    )
    (comp (ref "R39")
      (value "100k")
      (footprint "eagle-import:AXIAL-0.3")
      (libsource (lib "eagle-import") (part "100KOHM-HORIZ-1/4W-1%"))
    )
    (comp (ref "R40")
      (value "100k")
      (footprint "eagle-import:AXIAL-0.3")
      (libsource (lib "eagle-import") (part "100KOHM-HORIZ-1/4W-1%"))
    )
    (comp (ref "R41")
      (value "100k")
      (footprint "eagle-import:AXIAL-0.3")
      (libsource (lib "eagle-import") (part "100KOHM-HORIZ-1/4W-1%"))
    )
    (comp (ref "R43")
      (value "100k")
      (footprint "eagle-import:AXIAL-0.3")
      (libsource (lib "eagle-import") (part "100KOHM-HORIZ-1/4W-1%"))
    )
    (comp (ref "R44")
      (value "100k")
      (footprint "eagle-import:AXIAL-0.3")
      (libsource (lib "eagle-import") (part "100KOHM-HORIZ-1/4W-1%"))
    )
    (comp (ref "R45")
      (value "100k")
      (footprint "eagle-import:AXIAL-0.3")
      (libsource (lib "eagle-import") (part "100KOHM-HORIZ-1/4W-1%"))
    )
    (comp (ref "R46")
      (value "100k")
      (footprint "eagle-import:AXIAL-0.3")
      (libsource (lib "eagle-import") (part "100KOHM-HORIZ-1/4W-1%"))
    )
    (comp (ref "SR_EN")
      (value "SN74HC595N")
      (footprint "eagle-import:DIP16")
      (libsource (lib "eagle-import") (part "74595NHC"))
    )
    (comp (ref "SR_PULSE")
      (value "SN74HC595N")
      (footprint "eagle-import:DIP16")
      (libsource (lib "eagle-import") (part "74595NHC"))
    )
    (comp (ref "VCC")
      (value "CONN_03X2NO_SILK")
      (footprint "eagle-import:2X3-NS")
      (libsource (lib "eagle-import") (part "CONN_03X2NO_SILK"))
    )
    (comp (ref "VL")
      (value "FROMARD")
      (footprint "eagle-import:2X3")
      (libsource (lib "eagle-import") (part "CONN_03X2FEMALE"))
    )
    (comp (ref "VR1")
      (value "200K")
      (footprint "eagle-import:TRIMPOT-PTH-3386U")
      (libsource (lib "eagle-import") (part "TRIMPOT-PTH-10MM-KNOB-1/2W-10%"))
    )
    (comp (ref "VR2")
      (value "200K")
      (footprint "eagle-import:TRIMPOT-PTH-3386U")
      (libsource (lib "eagle-import") (part "TRIMPOT-PTH-10MM-KNOB-1/2W-10%"))
    )
    (comp (ref "VR3")
      (value "200K")
      (footprint "eagle-import:TRIMPOT-PTH-3386U")
      (libsource (lib "eagle-import") (part "TRIMPOT-PTH-10MM-KNOB-1/2W-10%"))
    )
    (comp (ref "VR4")
      (value "200K")
      (footprint "eagle-import:TRIMPOT-PTH-3386U")
      (libsource (lib "eagle-import") (part "TRIMPOT-PTH-10MM-KNOB-1/2W-10%"))
    )
    (comp (ref "VR5")
      (value "200K")
      (footprint "eagle-import:TRIMPOT-PTH-3386U")
      (libsource (lib "eagle-import") (part "TRIMPOT-PTH-10MM-KNOB-1/2W-10%"))
    )
    (comp (ref "VR6")
      (value "200K")
      (footprint "eagle-import:TRIMPOT-PTH-3386U")
      (libsource (lib "eagle-import") (part "TRIMPOT-PTH-10MM-KNOB-1/2W-10%"))
    )
    (comp (ref "VR7")
      (value "200K")
      (footprint "eagle-import:TRIMPOT-PTH-3386U")
      (libsource (lib "eagle-import") (part "TRIMPOT-PTH-10MM-KNOB-1/2W-10%"))
    )
    (comp (ref "VR8")
      (value "200K")
      (footprint "eagle-import:TRIMPOT-PTH-3386U")
      (libsource (lib "eagle-import") (part "TRIMPOT-PTH-10MM-KNOB-1/2W-10%"))
    )
    (comp (ref "VR9")
      (value "2M")
      (footprint "eagle-import:TRIMPOT-PTH-3386U")
      (libsource (lib "eagle-import") (part "TRIMPOT-PTH-10MM-KNOB-1/2W-10%"))
    )
    (comp (ref "VR10")
      (value "10k")
      (footprint "eagle-import:TRIMPOT-PTH-3386U")
      (libsource (lib "eagle-import") (part "TRIMPOT-PTH-10MM-KNOB-1/2W-10%"))
    )
    (comp (ref "VR11")
      (value "10k")
      (footprint "eagle-import:TRIMPOT-PTH-3386U")
      (libsource (lib "eagle-import") (part "TRIMPOT-PTH-10MM-KNOB-1/2W-10%"))
    )
    (comp (ref "VR12")
      (value "10k")
      (footprint "eagle-import:TRIMPOT-PTH-3386U")
      (libsource (lib "eagle-import") (part "TRIMPOT-PTH-10MM-KNOB-1/2W-10%"))
    )
    (comp (ref "VR13")
      (value "10k")
      (footprint "eagle-import:TRIMPOT-PTH-3386U")
      (libsource (lib "eagle-import") (part "TRIMPOT-PTH-10MM-KNOB-1/2W-10%"))
    )
    (comp (ref "VR14")
      (value "10k")
      (footprint "eagle-import:TRIMPOT-PTH-3386U")
      (libsource (lib "eagle-import") (part "TRIMPOT-PTH-10MM-KNOB-1/2W-10%"))
    )
    (comp (ref "VR15")
      (value "10k")
      (footprint "eagle-import:TRIMPOT-PTH-3386U")
      (libsource (lib "eagle-import") (part "TRIMPOT-PTH-10MM-KNOB-1/2W-10%"))
    )
    (comp (ref "VR16")
      (value "10k")
      (footprint "eagle-import:TRIMPOT-PTH-3386U")
      (libsource (lib "eagle-import") (part "TRIMPOT-PTH-10MM-KNOB-1/2W-10%"))
    )
  )
  (nets
    (net (code "1") (name "/EN1") (class "Default")
      (node (ref "EN1") (pin "1") (pinfunction "1_1") (pintype "passive"))
      (node (ref "R5") (pin "P$1") (pinfunction "1_P$1") (pintype "passive"))
      (node (ref "SR_EN") (pin "15") (pinfunction "QA_15") (pintype "tri_state"))
    )
    (net (code "2") (name "/EN2") (class "Default")
      (node (ref "EN2") (pin "1") (pinfunction "1_1") (pintype "passive"))
      (node (ref "R43") (pin "P$1") (pinfunction "1_P$1") (pintype "passive"))
      (node (ref "SR_EN") (pin "1") (pinfunction "QB_1") (pintype "tri_state"))
    )
    (net (code "3") (name "/EN3") (class "Default")
      (node (ref "EN3") (pin "1") (pinfunction "1_1") (pintype "passive"))
      (node (ref "R38") (pin "P$1") (pinfunction "1_P$1") (pintype "passive"))
      (node (ref "SR_EN") (pin "2") (pinfunction "QC_2") (pintype "tri_state"))
    )
    (net (code "4") (name "/EN4") (class "Default")
      (node (ref "EN4") (pin "1") (pinfunction "1_1") (pintype "passive"))
      (node (ref "R33") (pin "P$1") (pinfunction "1_P$1") (pintype "passive"))
      (node (ref "SR_EN") (pin "3") (pinfunction "QD_3") (pintype "tri_state"))
    )
    (net (code "5") (name "/EN5") (class "Default")
      (node (ref "EN5") (pin "1") (pinfunction "1_1") (pintype "passive"))
      (node (ref "R28") (pin "P$1") (pinfunction "1_P$1") (pintype "passive"))
      (node (ref "SR_EN") (pin "4") (pinfunction "QE_4") (pintype "tri_state"))
    )
    (net (code "6") (name "/EN6") (class "Default")
      (node (ref "EN6") (pin "1") (pinfunction "1_1") (pintype "passive"))
      (node (ref "R23") (pin "P$1") (pinfunction "1_P$1") (pintype "passive"))
      (node (ref "SR_EN") (pin "5") (pinfunction "QF_5") (pintype "tri_state"))
    )
    (net (code "7") (name "/EN7") (class "Default")
      (node (ref "EN7") (pin "1") (pinfunction "1_1") (pintype "passive"))
      (node (ref "R18") (pin "P$1") (pinfunction "1_P$1") (pintype "passive"))
      (node (ref "SR_EN") (pin "6") (pinfunction "QG_6") (pintype "tri_state"))
    )
    (net (code "8") (name "/EN8") (class "Default")
      (node (ref "EN8") (pin "1") (pinfunction "1_1") (pintype "passive"))
      (node (ref "R13") (pin "P$1") (pinfunction "1_P$1") (pintype "passive"))
      (node (ref "SR_EN") (pin "7") (pinfunction "QH_7") (pintype "tri_state"))
    )
    (net (code "9") (name "/GND") (class "Default")
      (node (ref "2N1") (pin "E") (pinfunction "E_E") (pintype "passive"))
      (node (ref "2N2") (pin "E") (pinfunction "E_E") (pintype "passive"))
      (node (ref "2N3") (pin "E") (pinfunction "E_E") (pintype "passive"))
      (node (ref "2N3904EN1") (pin "3") (pinfunction "E_3") (pintype "passive"))
      (node (ref "2N3904EN2") (pin "3") (pinfunction "E_3") (pintype "passive"))
      (node (ref "2N3904EN3") (pin "3") (pinfunction "E_3") (pintype "passive"))
      (node (ref "2N3904EN4") (pin "3") (pinfunction "E_3") (pintype "passive"))
      (node (ref "2N3904EN5") (pin "3") (pinfunction "E_3") (pintype "passive"))
      (node (ref "2N3904EN6") (pin "3") (pinfunction "E_3") (pintype "passive"))
      (node (ref "2N3904EN7") (pin "3") (pinfunction "E_3") (pintype "passive"))
      (node (ref "2N3904EN8") (pin "3") (pinfunction "E_3") (pintype "passive"))
      (node (ref "2N3904P1") (pin "3") (pinfunction "E_3") (pintype "passive"))
      (node (ref "2N3904P2") (pin "3") (pinfunction "E_3") (pintype "passive"))
      (node (ref "2N3904P3") (pin "3") (pinfunction "E_3") (pintype "passive"))
      (node (ref "2N3904P4") (pin "3") (pinfunction "E_3") (pintype "passive"))
      (node (ref "2N3904P5") (pin "3") (pinfunction "E_3") (pintype "passive"))
      (node (ref "2N3904P6") (pin "3") (pinfunction "E_3") (pintype "passive"))
      (node (ref "2N3904P7") (pin "3") (pinfunction "E_3") (pintype "passive"))
      (node (ref "2N3904P8") (pin "3") (pinfunction "E_3") (pintype "passive"))
      (node (ref "2N4") (pin "E") (pinfunction "E_E") (pintype "passive"))
      (node (ref "2N5") (pin "E") (pinfunction "E_E") (pintype "passive"))
      (node (ref "2N6") (pin "E") (pinfunction "E_E") (pintype "passive"))
      (node (ref "2N7") (pin "E") (pinfunction "E_E") (pintype "passive"))
      (node (ref "2N8") (pin "E") (pinfunction "E_E") (pintype "passive"))
      (node (ref "9VCC") (pin "GND") (pinfunction "GND_GND") (pintype "bidirectional"))
      (node (ref "9VCC") (pin "GNDBREAK") (pinfunction "GNDBREAK_GNDBREAK") (pintype "bidirectional"))
      (node (ref "COIL1") (pin "2") (pinfunction "2_2") (pintype "passive"))
      (node (ref "COIL2") (pin "2") (pinfunction "2_2") (pintype "passive"))
      (node (ref "COIL3") (pin "2") (pinfunction "2_2") (pintype "passive"))
      (node (ref "COIL4") (pin "2") (pinfunction "2_2") (pintype "passive"))
      (node (ref "COIL5") (pin "2") (pinfunction "2_2") (pintype "passive"))
      (node (ref "COIL6") (pin "2") (pinfunction "2_2") (pintype "passive"))
      (node (ref "COIL7") (pin "2") (pinfunction "2_2") (pintype "passive"))
      (node (ref "COIL8") (pin "2") (pinfunction "2_2") (pintype "passive"))
      (node (ref "COIL_AUX1") (pin "1") (pinfunction "1_1") (pintype "passive"))
      (node (ref "COIL_AUX2") (pin "1") (pinfunction "1_1") (pintype "passive"))
      (node (ref "COIL_AUX3") (pin "1") (pinfunction "1_1") (pintype "passive"))
      (node (ref "COIL_AUX4") (pin "1") (pinfunction "1_1") (pintype "passive"))
      (node (ref "COIL_AUX5") (pin "1") (pinfunction "1_1") (pintype "passive"))
      (node (ref "COIL_AUX6") (pin "1") (pinfunction "1_1") (pintype "passive"))
      (node (ref "COIL_AUX7") (pin "1") (pinfunction "1_1") (pintype "passive"))
      (node (ref "COIL_AUX8") (pin "1") (pinfunction "1_1") (pintype "passive"))
      (node (ref "CVCC1") (pin "-") (pinfunction "-_-") (pintype "passive"))
      (node (ref "CVCC2") (pin "-") (pinfunction "-_-") (pintype "passive"))
      (node (ref "C_EN") (pin "2") (pinfunction "2_2") (pintype "passive"))
      (node (ref "C_P") (pin "2") (pinfunction "2_2") (pintype "passive"))
      (node (ref "D1") (pin "A") (pinfunction "A_A") (pintype "passive"))
      (node (ref "D19") (pin "A") (pinfunction "A_A") (pintype "passive"))
      (node (ref "D2") (pin "A") (pinfunction "A_A") (pintype "passive"))
      (node (ref "D20") (pin "A") (pinfunction "A_A") (pintype "passive"))
      (node (ref "D21") (pin "A") (pinfunction "A_A") (pintype "passive"))
      (node (ref "D22") (pin "A") (pinfunction "A_A") (pintype "passive"))
      (node (ref "D23") (pin "A") (pinfunction "A_A") (pintype "passive"))
      (node (ref "D24") (pin "A") (pinfunction "A_A") (pintype "passive"))
      (node (ref "R1") (pin "P$1") (pinfunction "1_P$1") (pintype "passive"))
      (node (ref "R14") (pin "P$1") (pinfunction "1_P$1") (pintype "passive"))
      (node (ref "R16") (pin "P$1") (pinfunction "1_P$1") (pintype "passive"))
      (node (ref "R19") (pin "P$1") (pinfunction "1_P$1") (pintype "passive"))
      (node (ref "R2") (pin "P$1") (pinfunction "1_P$1") (pintype "passive"))
      (node (ref "R21") (pin "P$1") (pinfunction "1_P$1") (pintype "passive"))
      (node (ref "R24") (pin "P$1") (pinfunction "1_P$1") (pintype "passive"))
      (node (ref "R26") (pin "P$1") (pinfunction "1_P$1") (pintype "passive"))
      (node (ref "R29") (pin "P$1") (pinfunction "1_P$1") (pintype "passive"))
      (node (ref "R31") (pin "P$1") (pinfunction "1_P$1") (pintype "passive"))
      (node (ref "R34") (pin "P$1") (pinfunction "1_P$1") (pintype "passive"))
      (node (ref "R36") (pin "P$1") (pinfunction "1_P$1") (pintype "passive"))
      (node (ref "R39") (pin "P$1") (pinfunction "1_P$1") (pintype "passive"))
      (node (ref "R41") (pin "P$1") (pinfunction "1_P$1") (pintype "passive"))
      (node (ref "R44") (pin "P$1") (pinfunction "1_P$1") (pintype "passive"))
      (node (ref "R46") (pin "P$1") (pinfunction "1_P$1") (pintype "passive"))
      (node (ref "R6") (pin "P$1") (pinfunction "1_P$1") (pintype "passive"))
      (node (ref "R8") (pin "P$1") (pinfunction "1_P$1") (pintype "passive"))
      (node (ref "SR_EN") (pin "8") (pinfunction "GND_8") (pintype "power_in"))
      (node (ref "SR_PULSE") (pin "8") (pinfunction "GND_8") (pintype "power_in"))
      (node (ref "VCC") (pin "2") (pinfunction "2_2") (pintype "bidirectional"))
      (node (ref "VCC") (pin "4") (pinfunction "4_4") (pintype "bidirectional"))
      (node (ref "VCC") (pin "6") (pinfunction "6_6") (pintype "bidirectional"))
      (node (ref "VL") (pin "2") (pinfunction "2_2") (pintype "bidirectional"))
      (node (ref "VL") (pin "4") (pinfunction "4_4") (pintype "bidirectional"))
      (node (ref "VL") (pin "6") (pinfunction "6_6") (pintype "bidirectional"))
    )
    (net (code "10") (name "/LINK_EN") (class "Default")
      (node (ref "LINK_EN") (pin "1") (pinfunction "1_1") (pintype "passive"))
      (node (ref "SR_EN") (pin "9") (pinfunction "QH*_9") (pintype "tri_state"))
    )
    (net (code "11") (name "/LINK_P") (class "Default")
      (node (ref "LINK_P") (pin "1") (pinfunction "1_1") (pintype "passive"))
      (node (ref "SR_PULSE") (pin "9") (pinfunction "QH*_9") (pintype "tri_state"))
    )
    (net (code "12") (name "/OEBAR_EN") (class "Default")
      (node (ref "EN_PINS") (pin "1") (pinfunction "1_1") (pintype "passive"))
      (node (ref "R1") (pin "P$2") (pinfunction "2_P$2") (pintype "passive"))
      (node (ref "SR_EN") (pin "13") (pinfunction "G_13") (pintype "input"))
    )
    (net (code "13") (name "/OEBAR_P") (class "Default")
      (node (ref "P_PINS") (pin "1") (pinfunction "1_1") (pintype "passive"))
      (node (ref "R2") (pin "P$2") (pinfunction "2_P$2") (pintype "passive"))
      (node (ref "SR_PULSE") (pin "13") (pinfunction "G_13") (pintype "input"))
    )
    (net (code "14") (name "/PULSE1") (class "Default")
      (node (ref "PULSE1") (pin "1") (pinfunction "1_1") (pintype "passive"))
      (node (ref "R7") (pin "P$2") (pinfunction "2_P$2") (pintype "passive"))
      (node (ref "SR_PULSE") (pin "15") (pinfunction "QA_15") (pintype "tri_state"))
    )
    (net (code "15") (name "/PULSE2") (class "Default")
      (node (ref "PULSE2") (pin "1") (pinfunction "1_1") (pintype "passive"))
      (node (ref "R45") (pin "P$2") (pinfunction "2_P$2") (pintype "passive"))
      (node (ref "SR_PULSE") (pin "1") (pinfunction "QB_1") (pintype "tri_state"))
    )
    (net (code "16") (name "/PULSE3") (class "Default")
      (node (ref "PULSE3") (pin "1") (pinfunction "1_1") (pintype "passive"))
      (node (ref "R40") (pin "P$2") (pinfunction "2_P$2") (pintype "passive"))
      (node (ref "SR_PULSE") (pin "2") (pinfunction "QC_2") (pintype "tri_state"))
    )
    (net (code "17") (name "/PULSE4") (class "Default")
      (node (ref "PULSE4") (pin "1") (pinfunction "1_1") (pintype "passive"))
      (node (ref "R35") (pin "P$2") (pinfunction "2_P$2") (pintype "passive"))
      (node (ref "SR_PULSE") (pin "3") (pinfunction "QD_3") (pintype "tri_state"))
    )
    (net (code "18") (name "/PULSE5") (class "Default")
      (node (ref "PULSE5") (pin "1") (pinfunction "1_1") (pintype "passive"))
      (node (ref "R30") (pin "P$2") (pinfunction "2_P$2") (pintype "passive"))
      (node (ref "SR_PULSE") (pin "4") (pinfunction "QE_4") (pintype "tri_state"))
    )
    (net (code "19") (name "/PULSE6") (class "Default")
      (node (ref "PULSE6") (pin "1") (pinfunction "1_1") (pintype "passive"))
      (node (ref "R25") (pin "P$2") (pinfunction "2_P$2") (pintype "passive"))
      (node (ref "SR_PULSE") (pin "5") (pinfunction "QF_5") (pintype "tri_state"))
    )
    (net (code "20") (name "/PULSE7") (class "Default")
      (node (ref "PULSE7") (pin "1") (pinfunction "1_1") (pintype "passive"))
      (node (ref "R20") (pin "P$2") (pinfunction "2_P$2") (pintype "passive"))
      (node (ref "SR_PULSE") (pin "6") (pinfunction "QG_6") (pintype "tri_state"))
    )
    (net (code "21") (name "/PULSE8") (class "Default")
      (node (ref "PULSE8") (pin "1") (pinfunction "1_1") (pintype "passive"))
      (node (ref "R15") (pin "P$2") (pinfunction "2_P$2") (pintype "passive"))
      (node (ref "SR_PULSE") (pin "7") (pinfunction "QH_7") (pintype "tri_state"))
    )
    (net (code "22") (name "/RCLK_EN") (class "Default")
      (node (ref "EN_PINS") (pin "2") (pinfunction "2_2") (pintype "passive"))
      (node (ref "SR_EN") (pin "12") (pinfunction "RCK_12") (pintype "input"))
    )
    (net (code "23") (name "/RCLK_P") (class "Default")
      (node (ref "P_PINS") (pin "2") (pinfunction "2_2") (pintype "passive"))
      (node (ref "SR_PULSE") (pin "12") (pinfunction "RCK_12") (pintype "input"))
    )
    (net (code "24") (name "/SCK_EN") (class "Default")
      (node (ref "EN_PINS") (pin "3") (pinfunction "3_3") (pintype "passive"))
      (node (ref "SR_EN") (pin "11") (pinfunction "SCK_11") (pintype "input"))
    )
    (net (code "25") (name "/SCK_P") (class "Default")
      (node (ref "P_PINS") (pin "3") (pinfunction "3_3") (pintype "passive"))
      (node (ref "SR_PULSE") (pin "11") (pinfunction "SCK_11") (pintype "input"))
    )
    (net (code "26") (name "/SER_EN") (class "Default")
      (node (ref "EN_PINS") (pin "4") (pinfunction "4_4") (pintype "passive"))
      (node (ref "SR_EN") (pin "14") (pinfunction "SER_14") (pintype "input"))
    )
    (net (code "27") (name "/SER_P") (class "Default")
      (node (ref "P_PINS") (pin "4") (pinfunction "4_4") (pintype "passive"))
      (node (ref "SR_PULSE") (pin "14") (pinfunction "SER_14") (pintype "input"))
    )
    (net (code "28") (name "/VCC") (class "Default")
      (node (ref "9VCC") (pin "PWR") (pinfunction "PWR_PWR") (pintype "bidirectional"))
      (node (ref "CVCC1") (pin "+") (pinfunction "+_+") (pintype "passive"))
      (node (ref "CVCC2") (pin "+") (pinfunction "+_+") (pintype "passive"))
      (node (ref "PN2907EN1") (pin "E") (pinfunction "E_E") (pintype "passive"))
      (node (ref "PN2907EN2") (pin "E") (pinfunction "E_E") (pintype "passive"))
      (node (ref "PN2907EN3") (pin "E") (pinfunction "E_E") (pintype "passive"))
      (node (ref "PN2907EN4") (pin "E") (pinfunction "E_E") (pintype "passive"))
      (node (ref "PN2907EN5") (pin "E") (pinfunction "E_E") (pintype "passive"))
      (node (ref "PN2907EN6") (pin "E") (pinfunction "E_E") (pintype "passive"))
      (node (ref "PN2907EN7") (pin "E") (pinfunction "E_E") (pintype "passive"))
      (node (ref "PN2907EN8") (pin "E") (pinfunction "E_E") (pintype "passive"))
      (node (ref "PN2907P1") (pin "E") (pinfunction "E_E") (pintype "passive"))
      (node (ref "PN2907P2") (pin "E") (pinfunction "E_E") (pintype "passive"))
      (node (ref "PN2907P3") (pin "E") (pinfunction "E_E") (pintype "passive"))
      (node (ref "PN2907P4") (pin "E") (pinfunction "E_E") (pintype "passive"))
      (node (ref "PN2907P5") (pin "E") (pinfunction "E_E") (pintype "passive"))
      (node (ref "PN2907P6") (pin "E") (pinfunction "E_E") (pintype "passive"))
      (node (ref "PN2907P7") (pin "E") (pinfunction "E_E") (pintype "passive"))
      (node (ref "PN2907P8") (pin "E") (pinfunction "E_E") (pintype "passive"))
      (node (ref "VCC") (pin "1") (pinfunction "1_1") (pintype "bidirectional"))
      (node (ref "VCC") (pin "3") (pinfunction "3_3") (pintype "bidirectional"))
      (node (ref "VCC") (pin "5") (pinfunction "5_5") (pintype "bidirectional"))
    )
    (net (code "29") (name "/VL") (class "Default")
      (node (ref "C_EN") (pin "1") (pinfunction "1_1") (pintype "passive"))
      (node (ref "C_P") (pin "1") (pinfunction "1_1") (pintype "passive"))
      (node (ref "SR_EN") (pin "10") (pinfunction "SCL_10") (pintype "input"))
      (node (ref "SR_EN") (pin "16") (pinfunction "VCC_16") (pintype "power_in"))
      (node (ref "SR_PULSE") (pin "10") (pinfunction "SCL_10") (pintype "input"))
      (node (ref "SR_PULSE") (pin "16") (pinfunction "VCC_16") (pintype "power_in"))
      (node (ref "VL") (pin "1") (pinfunction "1_1") (pintype "bidirectional"))
      (node (ref "VL") (pin "3") (pinfunction "3_3") (pintype "bidirectional"))
      (node (ref "VL") (pin "5") (pinfunction "5_5") (pintype "bidirectional"))
    )
    (net (code "30") (name "Net-(2N1-PadC)") (class "Default")
      (node (ref "2N1") (pin "C") (pinfunction "C_C") (pintype "passive"))
      (node (ref "Q1") (pin "B") (pinfunction "B_B") (pintype "passive"))
    )
    (net (code "31") (name "Net-(2N2-PadC)") (class "Default")
      (node (ref "2N2") (pin "C") (pinfunction "C_C") (pintype "passive"))
      (node (ref "Q9") (pin "B") (pinfunction "B_B") (pintype "passive"))
    )
    (net (code "32") (name "Net-(2N3-PadC)") (class "Default")
      (node (ref "2N3") (pin "C") (pinfunction "C_C") (pintype "passive"))
      (node (ref "Q8") (pin "B") (pinfunction "B_B") (pintype "passive"))
    )
    (net (code "33") (name "Net-(2N4-PadC)") (class "Default")
      (node (ref "2N4") (pin "C") (pinfunction "C_C") (pintype "passive"))
      (node (ref "Q7") (pin "B") (pinfunction "B_B") (pintype "passive"))
    )
    (net (code "34") (name "Net-(2N5-PadC)") (class "Default")
      (node (ref "2N5") (pin "C") (pinfunction "C_C") (pintype "passive"))
      (node (ref "Q6") (pin "B") (pinfunction "B_B") (pintype "passive"))
    )
    (net (code "35") (name "Net-(2N6-PadC)") (class "Default")
      (node (ref "2N6") (pin "C") (pinfunction "C_C") (pintype "passive"))
      (node (ref "Q5") (pin "B") (pinfunction "B_B") (pintype "passive"))
    )
    (net (code "36") (name "Net-(2N7-PadC)") (class "Default")
      (node (ref "2N7") (pin "C") (pinfunction "C_C") (pintype "passive"))
      (node (ref "Q4") (pin "B") (pinfunction "B_B") (pintype "passive"))
    )
    (net (code "37") (name "Net-(2N8-PadC)") (class "Default")
      (node (ref "2N8") (pin "C") (pinfunction "C_C") (pintype "passive"))
      (node (ref "Q2") (pin "B") (pinfunction "B_B") (pintype "passive"))
    )
    (net (code "38") (name "Net-(2N3904EN1-B)") (class "Default")
      (node (ref "2N3904EN1") (pin "2") (pinfunction "B_2") (pintype "passive"))
      (node (ref "R5") (pin "P$2") (pinfunction "2_P$2") (pintype "passive"))
      (node (ref "R6") (pin "P$2") (pinfunction "2_P$2") (pintype "passive"))
    )
    (net (code "39") (name "Net-(2N3904EN1-C)") (class "Default")
      (node (ref "2N3904EN1") (pin "1") (pinfunction "C_1") (pintype "passive"))
      (node (ref "PN2907EN1") (pin "B") (pinfunction "B_B") (pintype "passive"))
    )
    (net (code "40") (name "Net-(2N3904EN2-B)") (class "Default")
      (node (ref "2N3904EN2") (pin "2") (pinfunction "B_2") (pintype "passive"))
      (node (ref "R13") (pin "P$2") (pinfunction "2_P$2") (pintype "passive"))
      (node (ref "R14") (pin "P$2") (pinfunction "2_P$2") (pintype "passive"))
    )
    (net (code "41") (name "Net-(2N3904EN2-C)") (class "Default")
      (node (ref "2N3904EN2") (pin "1") (pinfunction "C_1") (pintype "passive"))
      (node (ref "PN2907EN2") (pin "B") (pinfunction "B_B") (pintype "passive"))
    )
    (net (code "42") (name "Net-(2N3904EN3-B)") (class "Default")
      (node (ref "2N3904EN3") (pin "2") (pinfunction "B_2") (pintype "passive"))
      (node (ref "R18") (pin "P$2") (pinfunction "2_P$2") (pintype "passive"))
      (node (ref "R19") (pin "P$2") (pinfunction "2_P$2") (pintype "passive"))
    )
    (net (code "43") (name "Net-(2N3904EN3-C)") (class "Default")
      (node (ref "2N3904EN3") (pin "1") (pinfunction "C_1") (pintype "passive"))
      (node (ref "PN2907EN3") (pin "B") (pinfunction "B_B") (pintype "passive"))
    )
    (net (code "44") (name "Net-(2N3904EN4-B)") (class "Default")
      (node (ref "2N3904EN4") (pin "2") (pinfunction "B_2") (pintype "passive"))
      (node (ref "R23") (pin "P$2") (pinfunction "2_P$2") (pintype "passive"))
      (node (ref "R24") (pin "P$2") (pinfunction "2_P$2") (pintype "passive"))
    )
    (net (code "45") (name "Net-(2N3904EN4-C)") (class "Default")
      (node (ref "2N3904EN4") (pin "1") (pinfunction "C_1") (pintype "passive"))
      (node (ref "PN2907EN4") (pin "B") (pinfunction "B_B") (pintype "passive"))
    )
    (net (code "46") (name "Net-(2N3904EN5-B)") (class "Default")
      (node (ref "2N3904EN5") (pin "2") (pinfunction "B_2") (pintype "passive"))
      (node (ref "R28") (pin "P$2") (pinfunction "2_P$2") (pintype "passive"))
      (node (ref "R29") (pin "P$2") (pinfunction "2_P$2") (pintype "passive"))
    )
    (net (code "47") (name "Net-(2N3904EN5-C)") (class "Default")
      (node (ref "2N3904EN5") (pin "1") (pinfunction "C_1") (pintype "passive"))
      (node (ref "PN2907EN5") (pin "B") (pinfunction "B_B") (pintype "passive"))
    )
    (net (code "48") (name "Net-(2N3904EN6-B)") (class "Default")
      (node (ref "2N3904EN6") (pin "2") (pinfunction "B_2") (pintype "passive"))
      (node (ref "R33") (pin "P$2") (pinfunction "2_P$2") (pintype "passive"))
      (node (ref "R34") (pin "P$2") (pinfunction "2_P$2") (pintype "passive"))
    )
    (net (code "49") (name "Net-(2N3904EN6-C)") (class "Default")
      (node (ref "2N3904EN6") (pin "1") (pinfunction "C_1") (pintype "passive"))
      (node (ref "PN2907EN6") (pin "B") (pinfunction "B_B") (pintype "passive"))
    )
    (net (code "50") (name "Net-(2N3904EN7-B)") (class "Default")
      (node (ref "2N3904EN7") (pin "2") (pinfunction "B_2") (pintype "passive"))
      (node (ref "R38") (pin "P$2") (pinfunction "2_P$2") (pintype "passive"))
      (node (ref "R39") (pin "P$2") (pinfunction "2_P$2") (pintype "passive"))
    )
    (net (code "51") (name "Net-(2N3904EN7-C)") (class "Default")
      (node (ref "2N3904EN7") (pin "1") (pinfunction "C_1") (pintype "passive"))
      (node (ref "PN2907EN7") (pin "B") (pinfunction "B_B") (pintype "passive"))
    )
    (net (code "52") (name "Net-(2N3904EN8-B)") (class "Default")
      (node (ref "2N3904EN8") (pin "2") (pinfunction "B_2") (pintype "passive"))
      (node (ref "R43") (pin "P$2") (pinfunction "2_P$2") (pintype "passive"))
      (node (ref "R44") (pin "P$2") (pinfunction "2_P$2") (pintype "passive"))
    )
    (net (code "53") (name "Net-(2N3904EN8-C)") (class "Default")
      (node (ref "2N3904EN8") (pin "1") (pinfunction "C_1") (pintype "passive"))
      (node (ref "PN2907EN8") (pin "B") (pinfunction "B_B") (pintype "passive"))
    )
    (net (code "54") (name "Net-(2N3904P1-B)") (class "Default")
      (node (ref "2N3904P1") (pin "2") (pinfunction "B_2") (pintype "passive"))
      (node (ref "R7") (pin "P$1") (pinfunction "1_P$1") (pintype "passive"))
      (node (ref "R8") (pin "P$2") (pinfunction "2_P$2") (pintype "passive"))
    )
    (net (code "55") (name "Net-(2N3904P1-C)") (class "Default")
      (node (ref "2N3904P1") (pin "1") (pinfunction "C_1") (pintype "passive"))
      (node (ref "PN2907P1") (pin "B") (pinfunction "B_B") (pintype "passive"))
    )
    (net (code "56") (name "Net-(2N3904P2-B)") (class "Default")
      (node (ref "2N3904P2") (pin "2") (pinfunction "B_2") (pintype "passive"))
      (node (ref "R15") (pin "P$1") (pinfunction "1_P$1") (pintype "passive"))
      (node (ref "R16") (pin "P$2") (pinfunction "2_P$2") (pintype "passive"))
    )
    (net (code "57") (name "Net-(2N3904P2-C)") (class "Default")
      (node (ref "2N3904P2") (pin "1") (pinfunction "C_1") (pintype "passive"))
      (node (ref "PN2907P2") (pin "B") (pinfunction "B_B") (pintype "passive"))
    )
    (net (code "58") (name "Net-(2N3904P3-B)") (class "Default")
      (node (ref "2N3904P3") (pin "2") (pinfunction "B_2") (pintype "passive"))
      (node (ref "R20") (pin "P$1") (pinfunction "1_P$1") (pintype "passive"))
      (node (ref "R21") (pin "P$2") (pinfunction "2_P$2") (pintype "passive"))
    )
    (net (code "59") (name "Net-(2N3904P3-C)") (class "Default")
      (node (ref "2N3904P3") (pin "1") (pinfunction "C_1") (pintype "passive"))
      (node (ref "PN2907P3") (pin "B") (pinfunction "B_B") (pintype "passive"))
    )
    (net (code "60") (name "Net-(2N3904P4-B)") (class "Default")
      (node (ref "2N3904P4") (pin "2") (pinfunction "B_2") (pintype "passive"))
      (node (ref "R25") (pin "P$1") (pinfunction "1_P$1") (pintype "passive"))
      (node (ref "R26") (pin "P$2") (pinfunction "2_P$2") (pintype "passive"))
    )
    (net (code "61") (name "Net-(2N3904P4-C)") (class "Default")
      (node (ref "2N3904P4") (pin "1") (pinfunction "C_1") (pintype "passive"))
      (node (ref "PN2907P4") (pin "B") (pinfunction "B_B") (pintype "passive"))
    )
    (net (code "62") (name "Net-(2N3904P5-B)") (class "Default")
      (node (ref "2N3904P5") (pin "2") (pinfunction "B_2") (pintype "passive"))
      (node (ref "R30") (pin "P$1") (pinfunction "1_P$1") (pintype "passive"))
      (node (ref "R31") (pin "P$2") (pinfunction "2_P$2") (pintype "passive"))
    )
    (net (code "63") (name "Net-(2N3904P5-C)") (class "Default")
      (node (ref "2N3904P5") (pin "1") (pinfunction "C_1") (pintype "passive"))
      (node (ref "PN2907P5") (pin "B") (pinfunction "B_B") (pintype "passive"))
    )
    (net (code "64") (name "Net-(2N3904P6-B)") (class "Default")
      (node (ref "2N3904P6") (pin "2") (pinfunction "B_2") (pintype "passive"))
      (node (ref "R35") (pin "P$1") (pinfunction "1_P$1") (pintype "passive"))
      (node (ref "R36") (pin "P$2") (pinfunction "2_P$2") (pintype "passive"))
    )
    (net (code "65") (name "Net-(2N3904P6-C)") (class "Default")
      (node (ref "2N3904P6") (pin "1") (pinfunction "C_1") (pintype "passive"))
      (node (ref "PN2907P6") (pin "B") (pinfunction "B_B") (pintype "passive"))
    )
    (net (code "66") (name "Net-(2N3904P7-B)") (class "Default")
      (node (ref "2N3904P7") (pin "2") (pinfunction "B_2") (pintype "passive"))
      (node (ref "R40") (pin "P$1") (pinfunction "1_P$1") (pintype "passive"))
      (node (ref "R41") (pin "P$2") (pinfunction "2_P$2") (pintype "passive"))
    )
    (net (code "67") (name "Net-(2N3904P7-C)") (class "Default")
      (node (ref "2N3904P7") (pin "1") (pinfunction "C_1") (pintype "passive"))
      (node (ref "PN2907P7") (pin "B") (pinfunction "B_B") (pintype "passive"))
    )
    (net (code "68") (name "Net-(2N3904P8-B)") (class "Default")
      (node (ref "2N3904P8") (pin "2") (pinfunction "B_2") (pintype "passive"))
      (node (ref "R45") (pin "P$1") (pinfunction "1_P$1") (pintype "passive"))
      (node (ref "R46") (pin "P$2") (pinfunction "2_P$2") (pintype "passive"))
    )
    (net (code "69") (name "Net-(2N3904P8-C)") (class "Default")
      (node (ref "2N3904P8") (pin "1") (pinfunction "C_1") (pintype "passive"))
      (node (ref "PN2907P8") (pin "B") (pinfunction "B_B") (pintype "passive"))
    )
    (net (code "70") (name "Net-(D1-PadC)") (class "Default")
      (node (ref "D1") (pin "C") (pinfunction "C_C") (pintype "passive"))
      (node (ref "LED1") (pin "A") (pinfunction "A_A") (pintype "passive"))
    )
    (net (code "71") (name "Net-(D2-PadC)") (class "Default")
      (node (ref "D2") (pin "C") (pinfunction "C_C") (pintype "passive"))
      (node (ref "LED8") (pin "A") (pinfunction "A_A") (pintype "passive"))
    )
    (net (code "72") (name "Net-(D4-PadA)") (class "Default")
      (node (ref "D4") (pin "A") (pinfunction "A_A") (pintype "passive"))
      (node (ref "PN2907P1") (pin "C") (pinfunction "C_C") (pintype "passive"))
    )
    (net (code "73") (name "Net-(D6-PadA)") (class "Default")
      (node (ref "D6") (pin "A") (pinfunction "A_A") (pintype "passive"))
      (node (ref "PN2907P2") (pin "C") (pinfunction "C_C") (pintype "passive"))
    )
    (net (code "74") (name "Net-(D8-PadA)") (class "Default")
      (node (ref "D8") (pin "A") (pinfunction "A_A") (pintype "passive"))
      (node (ref "PN2907P3") (pin "C") (pinfunction "C_C") (pintype "passive"))
    )
    (net (code "75") (name "Net-(D10-PadA)") (class "Default")
      (node (ref "D10") (pin "A") (pinfunction "A_A") (pintype "passive"))
      (node (ref "PN2907P4") (pin "C") (pinfunction "C_C") (pintype "passive"))
    )
    (net (code "76") (name "Net-(D12-PadA)") (class "Default")
      (node (ref "D12") (pin "A") (pinfunction "A_A") (pintype "passive"))
      (node (ref "PN2907P5") (pin "C") (pinfunction "C_C") (pintype "passive"))
    )
    (net (code "77") (name "Net-(D14-PadA)") (class "Default")
      (node (ref "D14") (pin "A") (pinfunction "A_A") (pintype "passive"))
      (node (ref "PN2907P6") (pin "C") (pinfunction "C_C") (pintype "passive"))
    )
    (net (code "78") (name "Net-(D16-PadA)") (class "Default")
      (node (ref "D16") (pin "A") (pinfunction "A_A") (pintype "passive"))
      (node (ref "PN2907P7") (pin "C") (pinfunction "C_C") (pintype "passive"))
    )
    (net (code "79") (name "Net-(D18-PadA)") (class "Default")
      (node (ref "D18") (pin "A") (pinfunction "A_A") (pintype "passive"))
      (node (ref "PN2907P8") (pin "C") (pinfunction "C_C") (pintype "passive"))
    )
    (net (code "80") (name "Net-(D19-PadC)") (class "Default")
      (node (ref "D19") (pin "C") (pinfunction "C_C") (pintype "passive"))
      (node (ref "LED7") (pin "A") (pinfunction "A_A") (pintype "passive"))
    )
    (net (code "81") (name "Net-(D20-PadC)") (class "Default")
      (node (ref "D20") (pin "C") (pinfunction "C_C") (pintype "passive"))
      (node (ref "LED6") (pin "A") (pinfunction "A_A") (pintype "passive"))
    )
    (net (code "82") (name "Net-(D21-PadC)") (class "Default")
      (node (ref "D21") (pin "C") (pinfunction "C_C") (pintype "passive"))
      (node (ref "LED5") (pin "A") (pinfunction "A_A") (pintype "passive"))
    )
    (net (code "83") (name "Net-(D22-PadC)") (class "Default")
      (node (ref "D22") (pin "C") (pinfunction "C_C") (pintype "passive"))
      (node (ref "LED4") (pin "A") (pinfunction "A_A") (pintype "passive"))
    )
    (net (code "84") (name "Net-(D23-PadC)") (class "Default")
      (node (ref "D23") (pin "C") (pinfunction "C_C") (pintype "passive"))
      (node (ref "LED3") (pin "A") (pinfunction "A_A") (pintype "passive"))
    )
    (net (code "85") (name "Net-(D24-PadC)") (class "Default")
      (node (ref "D24") (pin "C") (pinfunction "C_C") (pintype "passive"))
      (node (ref "LED2") (pin "A") (pinfunction "A_A") (pintype "passive"))
    )
    (net (code "86") (name "Net-(LED1-C)") (class "Default")
      (node (ref "COIL1") (pin "1") (pinfunction "1_1") (pintype "passive"))
      (node (ref "COIL_AUX1") (pin "2") (pinfunction "2_2") (pintype "passive"))
      (node (ref "D4") (pin "C") (pinfunction "C_C") (pintype "passive"))
      (node (ref "LED1") (pin "K") (pinfunction "C_K") (pintype "passive"))
      (node (ref "Q1") (pin "C") (pinfunction "C_C") (pintype "passive"))
      (node (ref "VR1") (pin "2") (pinfunction "WIPER_2") (pintype "passive"))
      (node (ref "VR1") (pin "3") (pinfunction "CW_3") (pintype "passive"))
    )
    (net (code "87") (name "Net-(LED2-C)") (class "Default")
      (node (ref "COIL2") (pin "1") (pinfunction "1_1") (pintype "passive"))
      (node (ref "COIL_AUX2") (pin "2") (pinfunction "2_2") (pintype "passive"))
      (node (ref "D18") (pin "C") (pinfunction "C_C") (pintype "passive"))
      (node (ref "LED2") (pin "K") (pinfunction "C_K") (pintype "passive"))
      (node (ref "Q9") (pin "C") (pinfunction "C_C") (pintype "passive"))
      (node (ref "VR2") (pin "2") (pinfunction "WIPER_2") (pintype "passive"))
      (node (ref "VR2") (pin "3") (pinfunction "CW_3") (pintype "passive"))
    )
    (net (code "88") (name "Net-(LED3-C)") (class "Default")
      (node (ref "COIL3") (pin "1") (pinfunction "1_1") (pintype "passive"))
      (node (ref "COIL_AUX3") (pin "2") (pinfunction "2_2") (pintype "passive"))
      (node (ref "D16") (pin "C") (pinfunction "C_C") (pintype "passive"))
      (node (ref "LED3") (pin "K") (pinfunction "C_K") (pintype "passive"))
      (node (ref "Q8") (pin "C") (pinfunction "C_C") (pintype "passive"))
      (node (ref "VR3") (pin "2") (pinfunction "WIPER_2") (pintype "passive"))
      (node (ref "VR3") (pin "3") (pinfunction "CW_3") (pintype "passive"))
    )
    (net (code "89") (name "Net-(LED4-C)") (class "Default")
      (node (ref "COIL4") (pin "1") (pinfunction "1_1") (pintype "passive"))
      (node (ref "COIL_AUX4") (pin "2") (pinfunction "2_2") (pintype "passive"))
      (node (ref "D14") (pin "C") (pinfunction "C_C") (pintype "passive"))
      (node (ref "LED4") (pin "K") (pinfunction "C_K") (pintype "passive"))
      (node (ref "Q7") (pin "C") (pinfunction "C_C") (pintype "passive"))
      (node (ref "VR4") (pin "2") (pinfunction "WIPER_2") (pintype "passive"))
      (node (ref "VR4") (pin "3") (pinfunction "CW_3") (pintype "passive"))
    )
    (net (code "90") (name "Net-(LED5-C)") (class "Default")
      (node (ref "COIL5") (pin "1") (pinfunction "1_1") (pintype "passive"))
      (node (ref "COIL_AUX5") (pin "2") (pinfunction "2_2") (pintype "passive"))
      (node (ref "D12") (pin "C") (pinfunction "C_C") (pintype "passive"))
      (node (ref "LED5") (pin "K") (pinfunction "C_K") (pintype "passive"))
      (node (ref "Q6") (pin "C") (pinfunction "C_C") (pintype "passive"))
      (node (ref "VR5") (pin "2") (pinfunction "WIPER_2") (pintype "passive"))
      (node (ref "VR5") (pin "3") (pinfunction "CW_3") (pintype "passive"))
    )
    (net (code "91") (name "Net-(LED6-C)") (class "Default")
      (node (ref "COIL6") (pin "1") (pinfunction "1_1") (pintype "passive"))
      (node (ref "COIL_AUX6") (pin "2") (pinfunction "2_2") (pintype "passive"))
      (node (ref "D10") (pin "C") (pinfunction "C_C") (pintype "passive"))
      (node (ref "LED6") (pin "K") (pinfunction "C_K") (pintype "passive"))
      (node (ref "Q5") (pin "C") (pinfunction "C_C") (pintype "passive"))
      (node (ref "VR6") (pin "2") (pinfunction "WIPER_2") (pintype "passive"))
      (node (ref "VR6") (pin "3") (pinfunction "CW_3") (pintype "passive"))
    )
    (net (code "92") (name "Net-(LED7-C)") (class "Default")
      (node (ref "COIL7") (pin "1") (pinfunction "1_1") (pintype "passive"))
      (node (ref "COIL_AUX7") (pin "2") (pinfunction "2_2") (pintype "passive"))
      (node (ref "D8") (pin "C") (pinfunction "C_C") (pintype "passive"))
      (node (ref "LED7") (pin "K") (pinfunction "C_K") (pintype "passive"))
      (node (ref "Q4") (pin "C") (pinfunction "C_C") (pintype "passive"))
      (node (ref "VR7") (pin "2") (pinfunction "WIPER_2") (pintype "passive"))
      (node (ref "VR7") (pin "3") (pinfunction "CW_3") (pintype "passive"))
    )
    (net (code "93") (name "Net-(LED8-C)") (class "Default")
      (node (ref "COIL8") (pin "1") (pinfunction "1_1") (pintype "passive"))
      (node (ref "COIL_AUX8") (pin "2") (pinfunction "2_2") (pintype "passive"))
      (node (ref "D6") (pin "C") (pinfunction "C_C") (pintype "passive"))
      (node (ref "LED8") (pin "K") (pinfunction "C_K") (pintype "passive"))
      (node (ref "Q2") (pin "C") (pinfunction "C_C") (pintype "passive"))
      (node (ref "VR8") (pin "2") (pinfunction "WIPER_2") (pintype "passive"))
      (node (ref "VR8") (pin "3") (pinfunction "CW_3") (pintype "passive"))
    )
    (net (code "94") (name "Net-(R3-1)") (class "Default")
      (node (ref "D3") (pin "A") (pinfunction "A_A") (pintype "passive"))
      (node (ref "PN2907EN1") (pin "C") (pinfunction "C_C") (pintype "passive"))
      (node (ref "R3") (pin "P$1") (pinfunction "1_P$1") (pintype "passive"))
    )
    (net (code "95") (name "Net-(R3-2)") (class "Default")
      (node (ref "Q1") (pin "E") (pinfunction "E_E") (pintype "passive"))
      (node (ref "R3") (pin "P$2") (pinfunction "2_P$2") (pintype "passive"))
    )
    (net (code "96") (name "Net-(R4-1)") (class "Default")
      (node (ref "D5") (pin "A") (pinfunction "A_A") (pintype "passive"))
      (node (ref "PN2907EN2") (pin "C") (pinfunction "C_C") (pintype "passive"))
      (node (ref "R4") (pin "P$1") (pinfunction "1_P$1") (pintype "passive"))
    )
    (net (code "97") (name "Net-(R4-2)") (class "Default")
      (node (ref "Q2") (pin "E") (pinfunction "E_E") (pintype "passive"))
      (node (ref "R4") (pin "P$2") (pinfunction "2_P$2") (pintype "passive"))
    )
    (net (code "98") (name "Net-(R9-1)") (class "Default")
      (node (ref "D7") (pin "A") (pinfunction "A_A") (pintype "passive"))
      (node (ref "PN2907EN3") (pin "C") (pinfunction "C_C") (pintype "passive"))
      (node (ref "R9") (pin "P$1") (pinfunction "1_P$1") (pintype "passive"))
    )
    (net (code "99") (name "Net-(R9-2)") (class "Default")
      (node (ref "Q4") (pin "E") (pinfunction "E_E") (pintype "passive"))
      (node (ref "R9") (pin "P$2") (pinfunction "2_P$2") (pintype "passive"))
    )
    (net (code "100") (name "Net-(R10-1)") (class "Default")
      (node (ref "D9") (pin "A") (pinfunction "A_A") (pintype "passive"))
      (node (ref "PN2907EN4") (pin "C") (pinfunction "C_C") (pintype "passive"))
      (node (ref "R10") (pin "P$1") (pinfunction "1_P$1") (pintype "passive"))
    )
    (net (code "101") (name "Net-(R10-2)") (class "Default")
      (node (ref "Q5") (pin "E") (pinfunction "E_E") (pintype "passive"))
      (node (ref "R10") (pin "P$2") (pinfunction "2_P$2") (pintype "passive"))
    )
    (net (code "102") (name "Net-(R11-1)") (class "Default")
      (node (ref "D11") (pin "A") (pinfunction "A_A") (pintype "passive"))
      (node (ref "PN2907EN5") (pin "C") (pinfunction "C_C") (pintype "passive"))
      (node (ref "R11") (pin "P$1") (pinfunction "1_P$1") (pintype "passive"))
    )
    (net (code "103") (name "Net-(R11-2)") (class "Default")
      (node (ref "Q6") (pin "E") (pinfunction "E_E") (pintype "passive"))
      (node (ref "R11") (pin "P$2") (pinfunction "2_P$2") (pintype "passive"))
    )
    (net (code "104") (name "Net-(R12-1)") (class "Default")
      (node (ref "D17") (pin "A") (pinfunction "A_A") (pintype "passive"))
      (node (ref "PN2907EN8") (pin "C") (pinfunction "C_C") (pintype "passive"))
      (node (ref "R12") (pin "P$1") (pinfunction "1_P$1") (pintype "passive"))
    )
    (net (code "105") (name "Net-(R12-2)") (class "Default")
      (node (ref "Q9") (pin "E") (pinfunction "E_E") (pintype "passive"))
      (node (ref "R12") (pin "P$2") (pinfunction "2_P$2") (pintype "passive"))
    )
    (net (code "106") (name "Net-(R17-1)") (class "Default")
      (node (ref "D15") (pin "A") (pinfunction "A_A") (pintype "passive"))
      (node (ref "PN2907EN7") (pin "C") (pinfunction "C_C") (pintype "passive"))
      (node (ref "R17") (pin "P$1") (pinfunction "1_P$1") (pintype "passive"))
    )
    (net (code "107") (name "Net-(R17-2)") (class "Default")
      (node (ref "Q8") (pin "E") (pinfunction "E_E") (pintype "passive"))
      (node (ref "R17") (pin "P$2") (pinfunction "2_P$2") (pintype "passive"))
    )
    (net (code "108") (name "Net-(R22-1)") (class "Default")
      (node (ref "D13") (pin "A") (pinfunction "A_A") (pintype "passive"))
      (node (ref "PN2907EN6") (pin "C") (pinfunction "C_C") (pintype "passive"))
      (node (ref "R22") (pin "P$1") (pinfunction "1_P$1") (pintype "passive"))
    )
    (net (code "109") (name "Net-(R22-2)") (class "Default")
      (node (ref "Q7") (pin "E") (pinfunction "E_E") (pintype "passive"))
      (node (ref "R22") (pin "P$2") (pinfunction "2_P$2") (pintype "passive"))
    )
    (net (code "110") (name "Net-(VR1-CCW)") (class "Default")
      (node (ref "2N1") (pin "B") (pinfunction "B_B") (pintype "passive"))
      (node (ref "VR1") (pin "1") (pinfunction "CCW_1") (pintype "passive"))
      (node (ref "VR9") (pin "2") (pinfunction "WIPER_2") (pintype "passive"))
      (node (ref "VR9") (pin "3") (pinfunction "CW_3") (pintype "passive"))
    )
    (net (code "111") (name "Net-(VR9-CCW)") (class "Default")
      (node (ref "D3") (pin "C") (pinfunction "C_C") (pintype "passive"))
      (node (ref "VR9") (pin "1") (pinfunction "CCW_1") (pintype "passive"))
    )
    (net (code "112") (name "Net-(VR10-CCW)") (class "Default")
      (node (ref "D5") (pin "C") (pinfunction "C_C") (pintype "passive"))
      (node (ref "VR10") (pin "1") (pinfunction "CCW_1") (pintype "passive"))
    )
    (net (code "113") (name "Net-(VR10-CW)") (class "Default")
      (node (ref "2N8") (pin "B") (pinfunction "B_B") (pintype "passive"))
      (node (ref "VR10") (pin "2") (pinfunction "WIPER_2") (pintype "passive"))
      (node (ref "VR10") (pin "3") (pinfunction "CW_3") (pintype "passive"))
      (node (ref "VR8") (pin "1") (pinfunction "CCW_1") (pintype "passive"))
    )
    (net (code "114") (name "Net-(VR11-CCW)") (class "Default")
      (node (ref "D7") (pin "C") (pinfunction "C_C") (pintype "passive"))
      (node (ref "VR11") (pin "1") (pinfunction "CCW_1") (pintype "passive"))
    )
    (net (code "115") (name "Net-(VR11-CW)") (class "Default")
      (node (ref "2N7") (pin "B") (pinfunction "B_B") (pintype "passive"))
      (node (ref "VR11") (pin "2") (pinfunction "WIPER_2") (pintype "passive"))
      (node (ref "VR11") (pin "3") (pinfunction "CW_3") (pintype "passive"))
      (node (ref "VR7") (pin "1") (pinfunction "CCW_1") (pintype "passive"))
    )
    (net (code "116") (name "Net-(VR12-CCW)") (class "Default")
      (node (ref "D9") (pin "C") (pinfunction "C_C") (pintype "passive"))
      (node (ref "VR12") (pin "1") (pinfunction "CCW_1") (pintype "passive"))
    )
    (net (code "117") (name "Net-(VR12-CW)") (class "Default")
      (node (ref "2N6") (pin "B") (pinfunction "B_B") (pintype "passive"))
      (node (ref "VR12") (pin "2") (pinfunction "WIPER_2") (pintype "passive"))
      (node (ref "VR12") (pin "3") (pinfunction "CW_3") (pintype "passive"))
      (node (ref "VR6") (pin "1") (pinfunction "CCW_1") (pintype "passive"))
    )
    (net (code "118") (name "Net-(VR13-CCW)") (class "Default")
      (node (ref "D11") (pin "C") (pinfunction "C_C") (pintype "passive"))
      (node (ref "VR13") (pin "1") (pinfunction "CCW_1") (pintype "passive"))
    )
    (net (code "119") (name "Net-(VR13-CW)") (class "Default")
      (node (ref "2N5") (pin "B") (pinfunction "B_B") (pintype "passive"))
      (node (ref "VR13") (pin "2") (pinfunction "WIPER_2") (pintype "passive"))
      (node (ref "VR13") (pin "3") (pinfunction "CW_3") (pintype "passive"))
      (node (ref "VR5") (pin "1") (pinfunction "CCW_1") (pintype "passive"))
    )
    (net (code "120") (name "Net-(VR14-CCW)") (class "Default")
      (node (ref "D17") (pin "C") (pinfunction "C_C") (pintype "passive"))
      (node (ref "VR14") (pin "1") (pinfunction "CCW_1") (pintype "passive"))
    )
    (net (code "121") (name "Net-(VR14-CW)") (class "Default")
      (node (ref "2N2") (pin "B") (pinfunction "B_B") (pintype "passive"))
      (node (ref "VR14") (pin "2") (pinfunction "WIPER_2") (pintype "passive"))
      (node (ref "VR14") (pin "3") (pinfunction "CW_3") (pintype "passive"))
      (node (ref "VR2") (pin "1") (pinfunction "CCW_1") (pintype "passive"))
    )
    (net (code "122") (name "Net-(VR15-CCW)") (class "Default")
      (node (ref "D15") (pin "C") (pinfunction "C_C") (pintype "passive"))
      (node (ref "VR15") (pin "1") (pinfunction "CCW_1") (pintype "passive"))
    )
    (net (code "123") (name "Net-(VR15-CW)") (class "Default")
      (node (ref "2N3") (pin "B") (pinfunction "B_B") (pintype "passive"))
      (node (ref "VR15") (pin "2") (pinfunction "WIPER_2") (pintype "passive"))
      (node (ref "VR15") (pin "3") (pinfunction "CW_3") (pintype "passive"))
      (node (ref "VR3") (pin "1") (pinfunction "CCW_1") (pintype "passive"))
    )
    (net (code "124") (name "Net-(VR16-CCW)") (class "Default")
      (node (ref "D13") (pin "C") (pinfunction "C_C") (pintype "passive"))
      (node (ref "VR16") (pin "1") (pinfunction "CCW_1") (pintype "passive"))
    )
    (net (code "125") (name "Net-(VR16-CW)") (class "Default")
      (node (ref "2N4") (pin "B") (pinfunction "B_B") (pintype "passive"))
      (node (ref "VR16") (pin "2") (pinfunction "WIPER_2") (pintype "passive"))
      (node (ref "VR16") (pin "3") (pinfunction "CW_3") (pintype "passive"))
      (node (ref "VR4") (pin "1") (pinfunction "CCW_1") (pintype "passive"))
    )
  )
)
